# PCB1.net
KiCad netlist of a schematic drawn in EAGLE
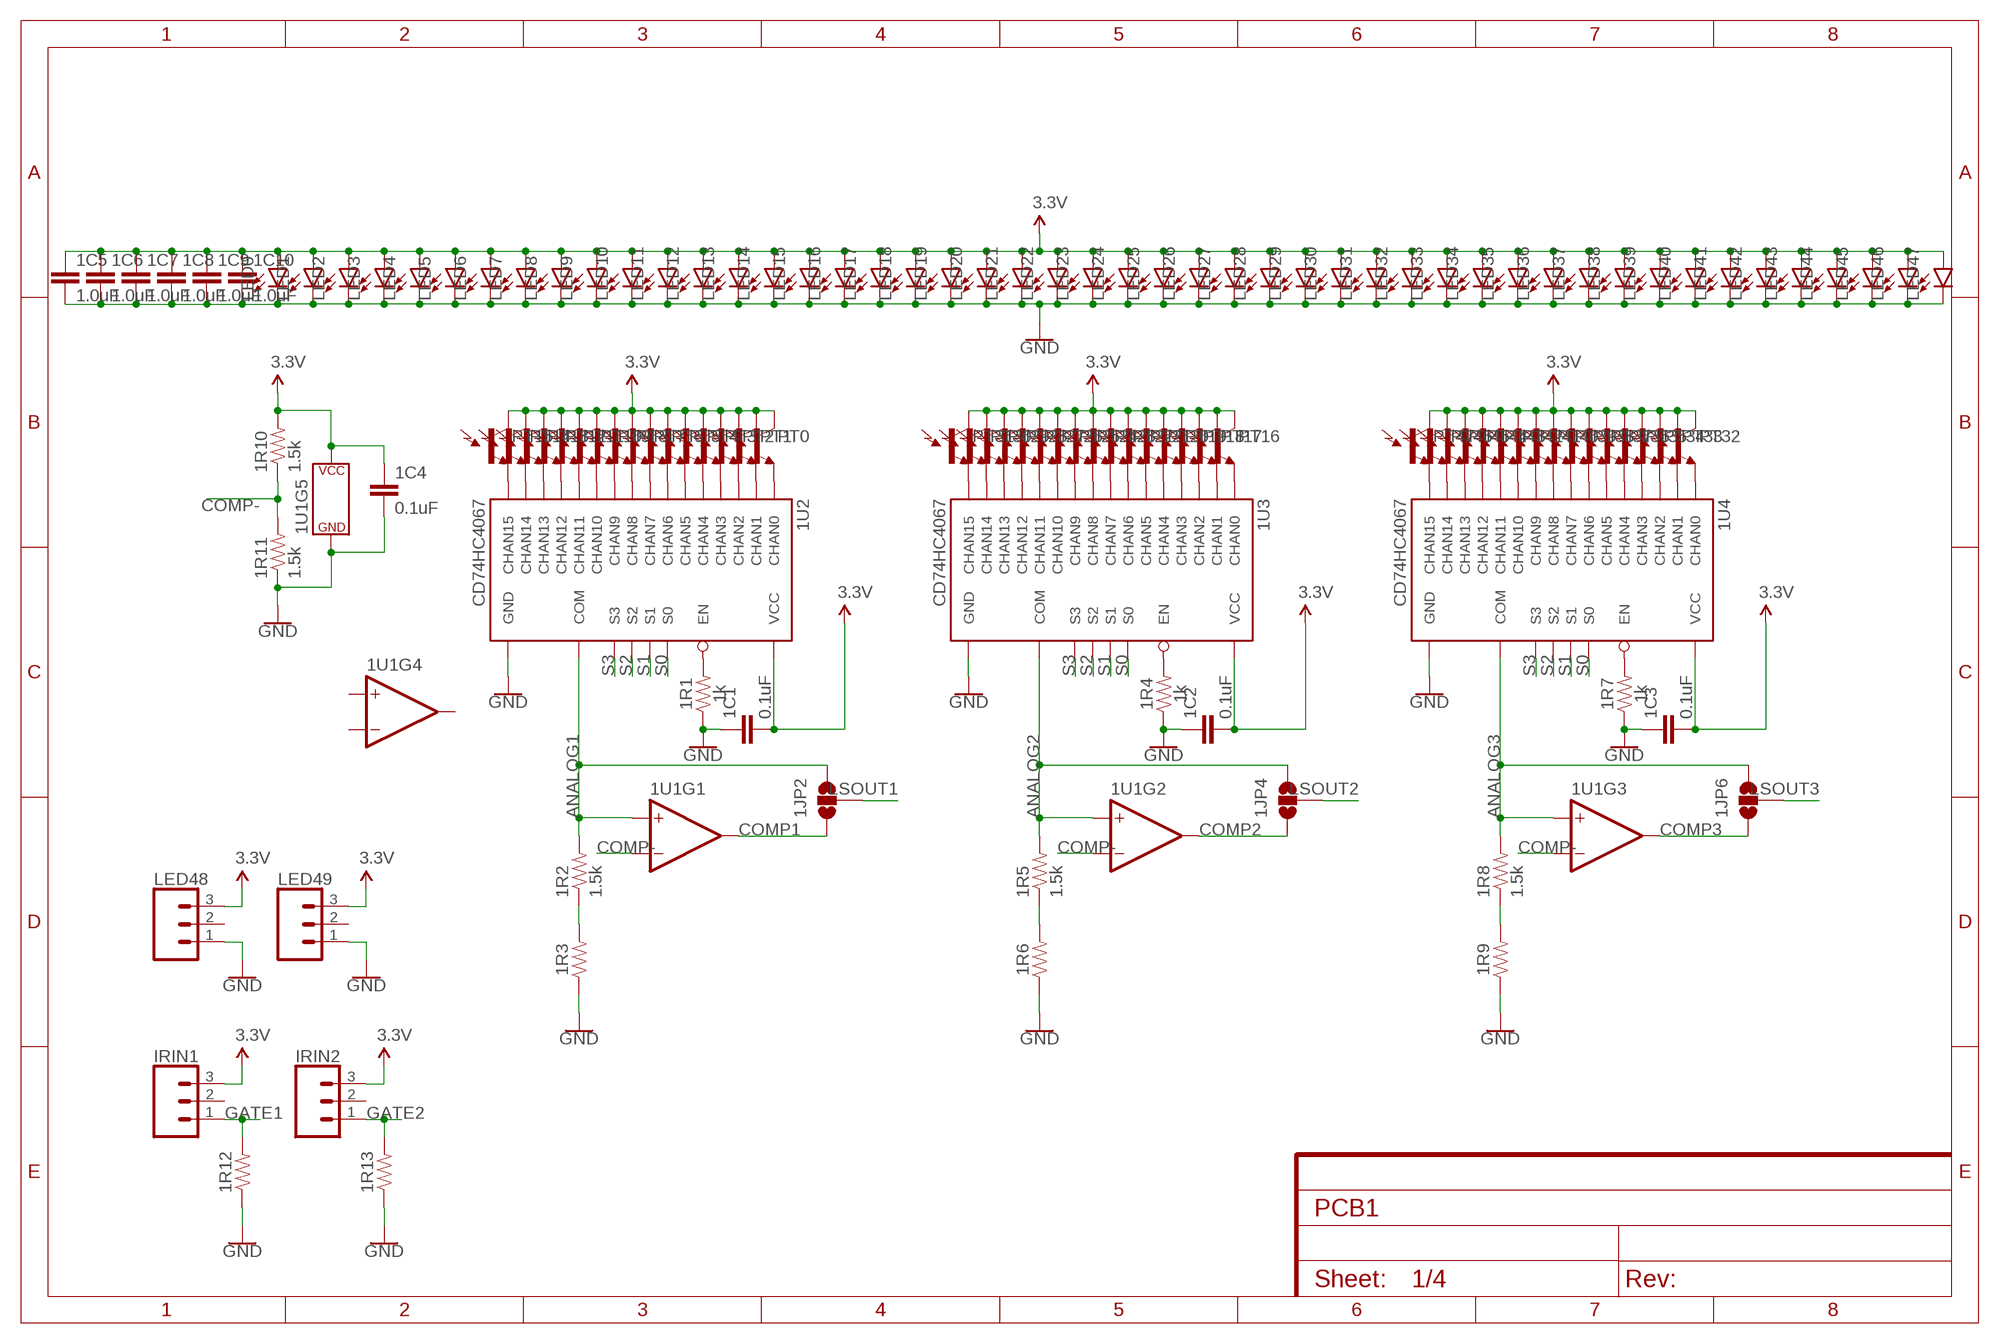
[diagram p0: schematic, sheet 1]
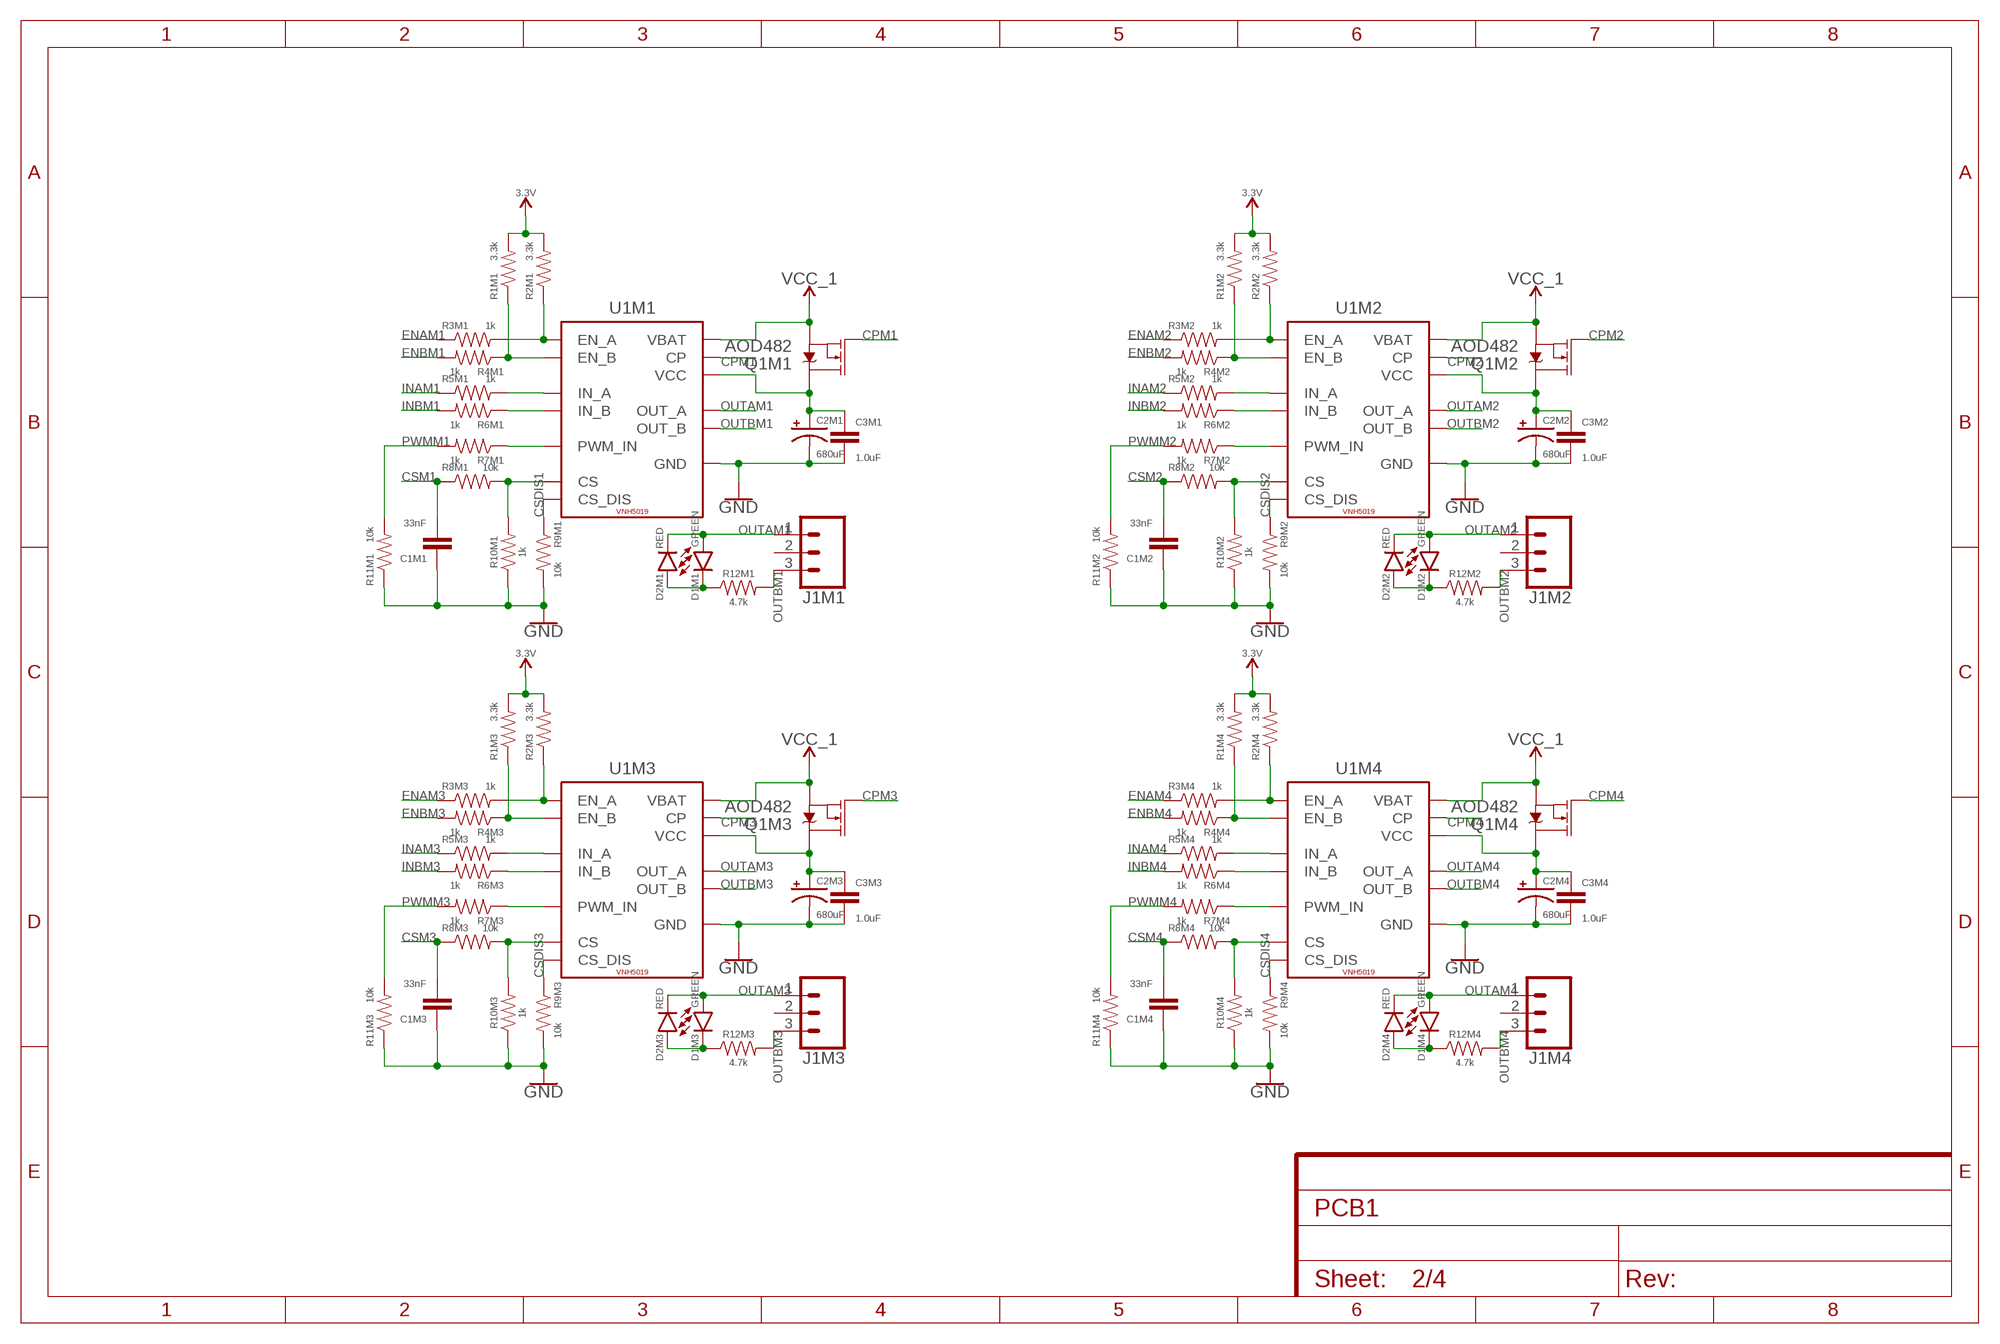
[diagram p1: schematic, sheet 2]
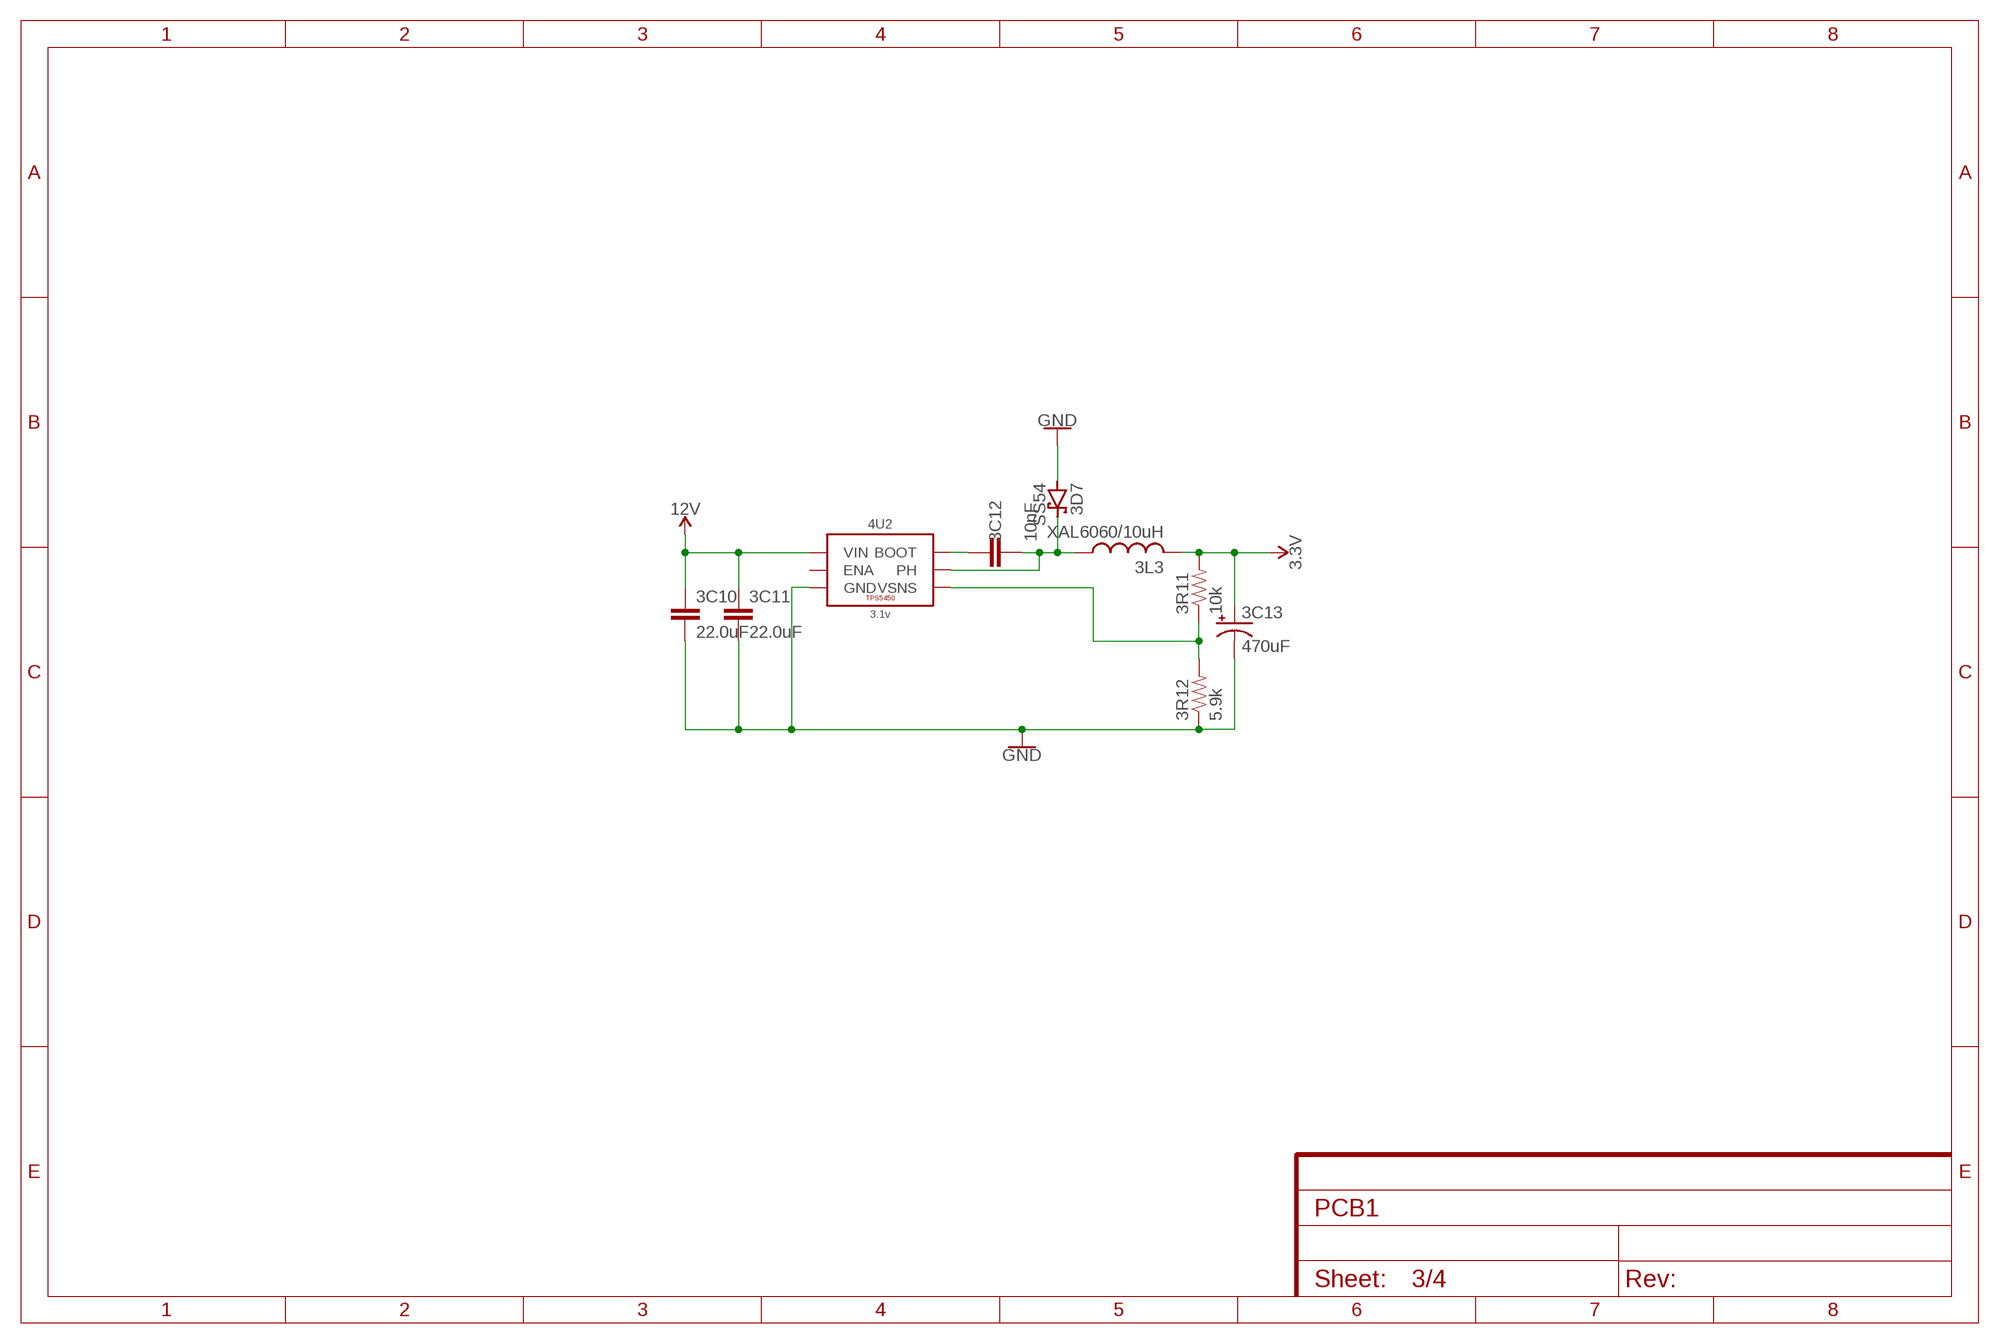
[diagram p2: schematic, sheet 3]
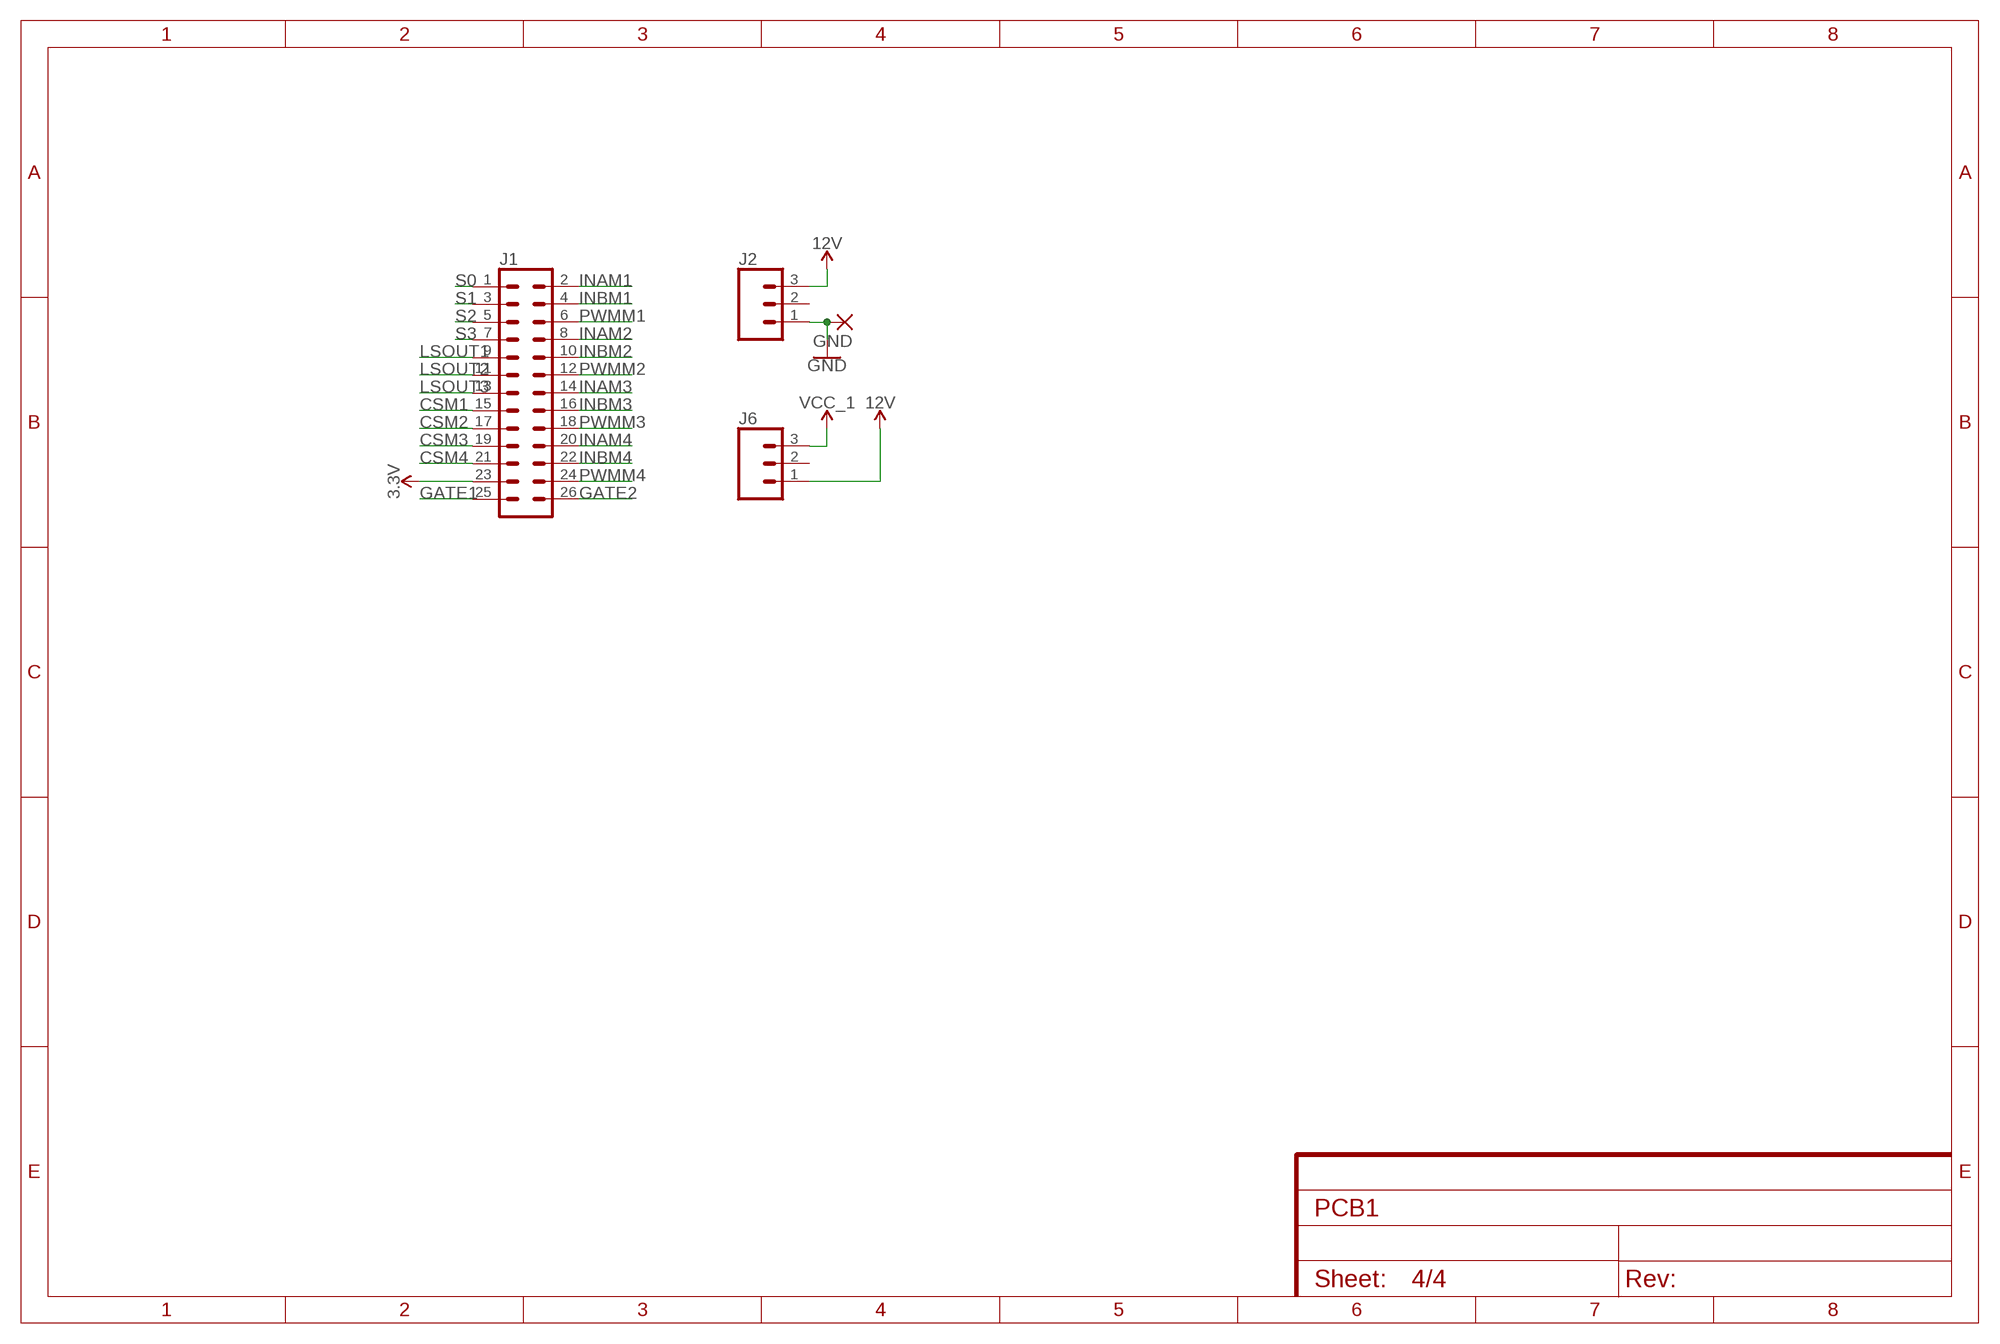
[diagram p3: schematic, sheet 4]

(export (version "E")
  (design (tool "Eeschema 10.0.6"))
  (components
    (comp (ref "C1M1")
      (value "33nF")
      (footprint "eagle-import:0603")
      (libsource (lib "eagle-import") (part "33NF-0603-50V-10%"))
    )
    (comp (ref "C1M2")
      (value "33nF")
      (footprint "eagle-import:0603")
      (libsource (lib "eagle-import") (part "33NF-0603-50V-10%"))
    )
    (comp (ref "C1M3")
      (value "33nF")
      (footprint "eagle-import:0603")
      (libsource (lib "eagle-import") (part "33NF-0603-50V-10%"))
    )
    (comp (ref "C1M4")
      (value "33nF")
      (footprint "eagle-import:0603")
      (libsource (lib "eagle-import") (part "33NF-0603-50V-10%"))
    )
    (comp (ref "C2M1")
      (value "680uF")
      (footprint "eagle-import:E3,5-8")
      (libsource (lib "eagle-import") (part "CPOL-USE3.5-8"))
    )
    (comp (ref "C2M2")
      (value "680uF")
      (footprint "eagle-import:E3,5-8")
      (libsource (lib "eagle-import") (part "CPOL-USE3.5-8"))
    )
    (comp (ref "C2M3")
      (value "680uF")
      (footprint "eagle-import:E3,5-8")
      (libsource (lib "eagle-import") (part "CPOL-USE3.5-8"))
    )
    (comp (ref "C2M4")
      (value "680uF")
      (footprint "eagle-import:E3,5-8")
      (libsource (lib "eagle-import") (part "CPOL-USE3.5-8"))
    )
    (comp (ref "C3M1")
      (value "1.0uF")
      (footprint "eagle-import:0603")
      (libsource (lib "eagle-import") (part "1.0UF-0603-16V-10%-X7R"))
    )
    (comp (ref "C3M2")
      (value "1.0uF")
      (footprint "eagle-import:0603")
      (libsource (lib "eagle-import") (part "1.0UF-0603-16V-10%-X7R"))
    )
    (comp (ref "C3M3")
      (value "1.0uF")
      (footprint "eagle-import:0603")
      (libsource (lib "eagle-import") (part "1.0UF-0603-16V-10%-X7R"))
    )
    (comp (ref "C3M4")
      (value "1.0uF")
      (footprint "eagle-import:0603")
      (libsource (lib "eagle-import") (part "1.0UF-0603-16V-10%-X7R"))
    )
    (comp (ref "D1M1")
      (value "GREEN")
      (footprint "eagle-import:LED-0603")
      (libsource (lib "eagle-import") (part "LED-GREEN0603"))
    )
    (comp (ref "D1M2")
      (value "GREEN")
      (footprint "eagle-import:LED-0603")
      (libsource (lib "eagle-import") (part "LED-GREEN0603"))
    )
    (comp (ref "D1M3")
      (value "GREEN")
      (footprint "eagle-import:LED-0603")
      (libsource (lib "eagle-import") (part "LED-GREEN0603"))
    )
    (comp (ref "D1M4")
      (value "GREEN")
      (footprint "eagle-import:LED-0603")
      (libsource (lib "eagle-import") (part "LED-GREEN0603"))
    )
    (comp (ref "D2M1")
      (value "RED")
      (footprint "eagle-import:LED-0603")
      (libsource (lib "eagle-import") (part "LED-RED0603"))
    )
    (comp (ref "D2M2")
      (value "RED")
      (footprint "eagle-import:LED-0603")
      (libsource (lib "eagle-import") (part "LED-RED0603"))
    )
    (comp (ref "D2M3")
      (value "RED")
      (footprint "eagle-import:LED-0603")
      (libsource (lib "eagle-import") (part "LED-RED0603"))
    )
    (comp (ref "D2M4")
      (value "RED")
      (footprint "eagle-import:LED-0603")
      (libsource (lib "eagle-import") (part "LED-RED0603"))
    )
    (comp (ref "J1M1")
      (value "CONN_03-SCREW-5MM")
      (footprint "eagle-import:SCREWTERMINAL-5MM-3")
      (libsource (lib "eagle-import") (part "CONN_03-SCREW-5MM"))
    )
    (comp (ref "J1M2")
      (value "CONN_03-SCREW-5MM")
      (footprint "eagle-import:SCREWTERMINAL-5MM-3")
      (libsource (lib "eagle-import") (part "CONN_03-SCREW-5MM"))
    )
    (comp (ref "J1M3")
      (value "CONN_03-SCREW-5MM")
      (footprint "eagle-import:SCREWTERMINAL-5MM-3")
      (libsource (lib "eagle-import") (part "CONN_03-SCREW-5MM"))
    )
    (comp (ref "J1M4")
      (value "CONN_03-SCREW-5MM")
      (footprint "eagle-import:SCREWTERMINAL-5MM-3")
      (libsource (lib "eagle-import") (part "CONN_03-SCREW-5MM"))
    )
    (comp (ref "Q1M1")
      (value "AOD482")
      (footprint "eagle-import:DPAK")
      (libsource (lib "eagle-import") (part "MOSFET-NCH-FDD8780"))
    )
    (comp (ref "Q1M2")
      (value "AOD482")
      (footprint "eagle-import:DPAK")
      (libsource (lib "eagle-import") (part "MOSFET-NCH-FDD8780"))
    )
    (comp (ref "Q1M3")
      (value "AOD482")
      (footprint "eagle-import:DPAK")
      (libsource (lib "eagle-import") (part "MOSFET-NCH-FDD8780"))
    )
    (comp (ref "Q1M4")
      (value "AOD482")
      (footprint "eagle-import:DPAK")
      (libsource (lib "eagle-import") (part "MOSFET-NCH-FDD8780"))
    )
    (comp (ref "R1M1")
      (value "3.3k")
      (footprint "eagle-import:0603")
      (libsource (lib "eagle-import") (part "3.3KOHM-0603-1/10W-1%"))
    )
    (comp (ref "R1M2")
      (value "3.3k")
      (footprint "eagle-import:0603")
      (libsource (lib "eagle-import") (part "3.3KOHM-0603-1/10W-1%"))
    )
    (comp (ref "R1M3")
      (value "3.3k")
      (footprint "eagle-import:0603")
      (libsource (lib "eagle-import") (part "3.3KOHM-0603-1/10W-1%"))
    )
    (comp (ref "R1M4")
      (value "3.3k")
      (footprint "eagle-import:0603")
      (libsource (lib "eagle-import") (part "3.3KOHM-0603-1/10W-1%"))
    )
    (comp (ref "R2M1")
      (value "3.3k")
      (footprint "eagle-import:0603")
      (libsource (lib "eagle-import") (part "3.3KOHM-0603-1/10W-1%"))
    )
    (comp (ref "R2M2")
      (value "3.3k")
      (footprint "eagle-import:0603")
      (libsource (lib "eagle-import") (part "3.3KOHM-0603-1/10W-1%"))
    )
    (comp (ref "R2M3")
      (value "3.3k")
      (footprint "eagle-import:0603")
      (libsource (lib "eagle-import") (part "3.3KOHM-0603-1/10W-1%"))
    )
    (comp (ref "R2M4")
      (value "3.3k")
      (footprint "eagle-import:0603")
      (libsource (lib "eagle-import") (part "3.3KOHM-0603-1/10W-1%"))
    )
    (comp (ref "R3M1")
      (value "1k")
      (footprint "eagle-import:0603")
      (libsource (lib "eagle-import") (part "1KOHM-0603-1/10W-1%"))
    )
    (comp (ref "R3M2")
      (value "1k")
      (footprint "eagle-import:0603")
      (libsource (lib "eagle-import") (part "1KOHM-0603-1/10W-1%"))
    )
    (comp (ref "R3M3")
      (value "1k")
      (footprint "eagle-import:0603")
      (libsource (lib "eagle-import") (part "1KOHM-0603-1/10W-1%"))
    )
    (comp (ref "R3M4")
      (value "1k")
      (footprint "eagle-import:0603")
      (libsource (lib "eagle-import") (part "1KOHM-0603-1/10W-1%"))
    )
    (comp (ref "R4M1")
      (value "1k")
      (footprint "eagle-import:0603")
      (libsource (lib "eagle-import") (part "1KOHM-0603-1/10W-1%"))
    )
    (comp (ref "R4M2")
      (value "1k")
      (footprint "eagle-import:0603")
      (libsource (lib "eagle-import") (part "1KOHM-0603-1/10W-1%"))
    )
    (comp (ref "R4M3")
      (value "1k")
      (footprint "eagle-import:0603")
      (libsource (lib "eagle-import") (part "1KOHM-0603-1/10W-1%"))
    )
    (comp (ref "R4M4")
      (value "1k")
      (footprint "eagle-import:0603")
      (libsource (lib "eagle-import") (part "1KOHM-0603-1/10W-1%"))
    )
    (comp (ref "R5M1")
      (value "1k")
      (footprint "eagle-import:0603")
      (libsource (lib "eagle-import") (part "1KOHM-0603-1/10W-1%"))
    )
    (comp (ref "R5M2")
      (value "1k")
      (footprint "eagle-import:0603")
      (libsource (lib "eagle-import") (part "1KOHM-0603-1/10W-1%"))
    )
    (comp (ref "R5M3")
      (value "1k")
      (footprint "eagle-import:0603")
      (libsource (lib "eagle-import") (part "1KOHM-0603-1/10W-1%"))
    )
    (comp (ref "R5M4")
      (value "1k")
      (footprint "eagle-import:0603")
      (libsource (lib "eagle-import") (part "1KOHM-0603-1/10W-1%"))
    )
    (comp (ref "R6M1")
      (value "1k")
      (footprint "eagle-import:0603")
      (libsource (lib "eagle-import") (part "1KOHM-0603-1/10W-1%"))
    )
    (comp (ref "R6M2")
      (value "1k")
      (footprint "eagle-import:0603")
      (libsource (lib "eagle-import") (part "1KOHM-0603-1/10W-1%"))
    )
    (comp (ref "R6M3")
      (value "1k")
      (footprint "eagle-import:0603")
      (libsource (lib "eagle-import") (part "1KOHM-0603-1/10W-1%"))
    )
    (comp (ref "R6M4")
      (value "1k")
      (footprint "eagle-import:0603")
      (libsource (lib "eagle-import") (part "1KOHM-0603-1/10W-1%"))
    )
    (comp (ref "R7M1")
      (value "1k")
      (footprint "eagle-import:0603")
      (libsource (lib "eagle-import") (part "1KOHM-0603-1/10W-1%"))
    )
    (comp (ref "R7M2")
      (value "1k")
      (footprint "eagle-import:0603")
      (libsource (lib "eagle-import") (part "1KOHM-0603-1/10W-1%"))
    )
    (comp (ref "R7M3")
      (value "1k")
      (footprint "eagle-import:0603")
      (libsource (lib "eagle-import") (part "1KOHM-0603-1/10W-1%"))
    )
    (comp (ref "R7M4")
      (value "1k")
      (footprint "eagle-import:0603")
      (libsource (lib "eagle-import") (part "1KOHM-0603-1/10W-1%"))
    )
    (comp (ref "R8M1")
      (value "10k")
      (footprint "eagle-import:0603")
      (libsource (lib "eagle-import") (part "10KOHM-0603-1/10W-1%"))
    )
    (comp (ref "R8M2")
      (value "10k")
      (footprint "eagle-import:0603")
      (libsource (lib "eagle-import") (part "10KOHM-0603-1/10W-1%"))
    )
    (comp (ref "R8M3")
      (value "10k")
      (footprint "eagle-import:0603")
      (libsource (lib "eagle-import") (part "10KOHM-0603-1/10W-1%"))
    )
    (comp (ref "R8M4")
      (value "10k")
      (footprint "eagle-import:0603")
      (libsource (lib "eagle-import") (part "10KOHM-0603-1/10W-1%"))
    )
    (comp (ref "R9M1")
      (value "10k")
      (footprint "eagle-import:0603")
      (libsource (lib "eagle-import") (part "10KOHM-0603-1/10W-1%"))
    )
    (comp (ref "R9M2")
      (value "10k")
      (footprint "eagle-import:0603")
      (libsource (lib "eagle-import") (part "10KOHM-0603-1/10W-1%"))
    )
    (comp (ref "R9M3")
      (value "10k")
      (footprint "eagle-import:0603")
      (libsource (lib "eagle-import") (part "10KOHM-0603-1/10W-1%"))
    )
    (comp (ref "R9M4")
      (value "10k")
      (footprint "eagle-import:0603")
      (libsource (lib "eagle-import") (part "10KOHM-0603-1/10W-1%"))
    )
    (comp (ref "R10M1")
      (value "1k")
      (footprint "eagle-import:0603")
      (libsource (lib "eagle-import") (part "1KOHM-0603-1/10W-1%"))
    )
    (comp (ref "R10M2")
      (value "1k")
      (footprint "eagle-import:0603")
      (libsource (lib "eagle-import") (part "1KOHM-0603-1/10W-1%"))
    )
    (comp (ref "R10M3")
      (value "1k")
      (footprint "eagle-import:0603")
      (libsource (lib "eagle-import") (part "1KOHM-0603-1/10W-1%"))
    )
    (comp (ref "R10M4")
      (value "1k")
      (footprint "eagle-import:0603")
      (libsource (lib "eagle-import") (part "1KOHM-0603-1/10W-1%"))
    )
    (comp (ref "R11M1")
      (value "10k")
      (footprint "eagle-import:0603")
      (libsource (lib "eagle-import") (part "10KOHM-0603-1/10W-1%"))
    )
    (comp (ref "R11M2")
      (value "10k")
      (footprint "eagle-import:0603")
      (libsource (lib "eagle-import") (part "10KOHM-0603-1/10W-1%"))
    )
    (comp (ref "R11M3")
      (value "10k")
      (footprint "eagle-import:0603")
      (libsource (lib "eagle-import") (part "10KOHM-0603-1/10W-1%"))
    )
    (comp (ref "R11M4")
      (value "10k")
      (footprint "eagle-import:0603")
      (libsource (lib "eagle-import") (part "10KOHM-0603-1/10W-1%"))
    )
    (comp (ref "R12M1")
      (value "4.7k")
      (footprint "eagle-import:0603")
      (libsource (lib "eagle-import") (part "4.7KOHM-0603-1/10W-1%"))
    )
    (comp (ref "R12M2")
      (value "4.7k")
      (footprint "eagle-import:0603")
      (libsource (lib "eagle-import") (part "4.7KOHM-0603-1/10W-1%"))
    )
    (comp (ref "R12M3")
      (value "4.7k")
      (footprint "eagle-import:0603")
      (libsource (lib "eagle-import") (part "4.7KOHM-0603-1/10W-1%"))
    )
    (comp (ref "R12M4")
      (value "4.7k")
      (footprint "eagle-import:0603")
      (libsource (lib "eagle-import") (part "4.7KOHM-0603-1/10W-1%"))
    )
    (comp (ref "U1M1")
      (value "VNH5019")
      (footprint "eagle-import:POWERSO-30")
      (libsource (lib "eagle-import") (part "VNH5019"))
    )
    (comp (ref "U1M2")
      (value "VNH5019")
      (footprint "eagle-import:POWERSO-30")
      (libsource (lib "eagle-import") (part "VNH5019"))
    )
    (comp (ref "U1M3")
      (value "VNH5019")
      (footprint "eagle-import:POWERSO-30")
      (libsource (lib "eagle-import") (part "VNH5019"))
    )
    (comp (ref "U1M4")
      (value "VNH5019")
      (footprint "eagle-import:POWERSO-30")
      (libsource (lib "eagle-import") (part "VNH5019"))
    )
    (comp (ref "1C1")
      (value "0.1uF")
      (footprint "eagle-import:0603")
      (libsource (lib "eagle-import") (part "0.1UF-0603-25V-5%"))
    )
    (comp (ref "1C2")
      (value "0.1uF")
      (footprint "eagle-import:0603")
      (libsource (lib "eagle-import") (part "0.1UF-0603-25V-5%"))
    )
    (comp (ref "1C3")
      (value "0.1uF")
      (footprint "eagle-import:0603")
      (libsource (lib "eagle-import") (part "0.1UF-0603-25V-5%"))
    )
    (comp (ref "1C4")
      (value "0.1uF")
      (footprint "eagle-import:0603")
      (libsource (lib "eagle-import") (part "0.1UF-0603-25V-5%"))
    )
    (comp (ref "1C5")
      (value "1.0uF")
      (footprint "eagle-import:0603")
      (libsource (lib "eagle-import") (part "1.0UF-0603-16V-10%-X7R"))
    )
    (comp (ref "1C6")
      (value "1.0uF")
      (footprint "eagle-import:0603")
      (libsource (lib "eagle-import") (part "1.0UF-0603-16V-10%-X7R"))
    )
    (comp (ref "1C7")
      (value "1.0uF")
      (footprint "eagle-import:0603")
      (libsource (lib "eagle-import") (part "1.0UF-0603-16V-10%-X7R"))
    )
    (comp (ref "1C8")
      (value "1.0uF")
      (footprint "eagle-import:0603")
      (libsource (lib "eagle-import") (part "1.0UF-0603-16V-10%-X7R"))
    )
    (comp (ref "1C9")
      (value "1.0uF")
      (footprint "eagle-import:0603")
      (libsource (lib "eagle-import") (part "1.0UF-0603-16V-10%-X7R"))
    )
    (comp (ref "1C10")
      (value "1.0uF")
      (footprint "eagle-import:0603")
      (libsource (lib "eagle-import") (part "1.0UF-0603-16V-10%-X7R"))
    )
    (comp (ref "1JP2")
      (value "JUMPER-SMT_3_NO_NO_SILK")
      (footprint "eagle-import:SMT-JUMPER_3_0-NO_TRACE_NO-SILK")
      (libsource (lib "eagle-import") (part "JUMPER-SMT_3_NO_NO_SILK"))
    )
    (comp (ref "1JP4")
      (value "JUMPER-SMT_3_NO_NO_SILK")
      (footprint "eagle-import:SMT-JUMPER_3_0-NO_TRACE_NO-SILK")
      (libsource (lib "eagle-import") (part "JUMPER-SMT_3_NO_NO_SILK"))
    )
    (comp (ref "1JP6")
      (value "JUMPER-SMT_3_NO_NO_SILK")
      (footprint "eagle-import:SMT-JUMPER_3_0-NO_TRACE_NO-SILK")
      (libsource (lib "eagle-import") (part "JUMPER-SMT_3_NO_NO_SILK"))
    )
    (comp (ref "1R1")
      (value "1k")
      (footprint "eagle-import:0603")
      (libsource (lib "eagle-import") (part "1KOHM-0603-1/10W-1%"))
    )
    (comp (ref "1R2")
      (value "1.5k")
      (footprint "eagle-import:0603")
      (libsource (lib "eagle-import") (part "1.5KOHM-0603-1/10W-1%"))
    )
    (comp (ref "1R3")
      (value "RESISTOR0603")
      (footprint "eagle-import:0603")
      (libsource (lib "eagle-import") (part "RESISTOR0603"))
    )
    (comp (ref "1R4")
      (value "1k")
      (footprint "eagle-import:0603")
      (libsource (lib "eagle-import") (part "1KOHM-0603-1/10W-1%"))
    )
    (comp (ref "1R5")
      (value "1.5k")
      (footprint "eagle-import:0603")
      (libsource (lib "eagle-import") (part "1.5KOHM-0603-1/10W-1%"))
    )
    (comp (ref "1R6")
      (value "RESISTOR0603")
      (footprint "eagle-import:0603")
      (libsource (lib "eagle-import") (part "RESISTOR0603"))
    )
    (comp (ref "1R7")
      (value "1k")
      (footprint "eagle-import:0603")
      (libsource (lib "eagle-import") (part "1KOHM-0603-1/10W-1%"))
    )
    (comp (ref "1R8")
      (value "1.5k")
      (footprint "eagle-import:0603")
      (libsource (lib "eagle-import") (part "1.5KOHM-0603-1/10W-1%"))
    )
    (comp (ref "1R9")
      (value "RESISTOR0603")
      (footprint "eagle-import:0603")
      (libsource (lib "eagle-import") (part "RESISTOR0603"))
    )
    (comp (ref "1R10")
      (value "1.5k")
      (footprint "eagle-import:0603")
      (libsource (lib "eagle-import") (part "1.5KOHM-0603-1/10W-1%"))
    )
    (comp (ref "1R11")
      (value "1.5k")
      (footprint "eagle-import:0603")
      (libsource (lib "eagle-import") (part "1.5KOHM-0603-1/10W-1%"))
    )
    (comp (ref "1R12")
      (value "RESISTOR0603")
      (footprint "eagle-import:0603")
      (libsource (lib "eagle-import") (part "RESISTOR0603"))
    )
    (comp (ref "1R13")
      (value "RESISTOR0603")
      (footprint "eagle-import:0603")
      (libsource (lib "eagle-import") (part "RESISTOR0603"))
    )
    (comp (ref "1U1")
      (value "LM339")
      (footprint "eagle-import:SOIC-14")
      (libsource (lib "eagle-import") (part "LM339"))
    )
    (comp (ref "1U2")
      (value "CD74HC4067")
      (footprint "eagle-import:SOIC-24")
      (libsource (lib "eagle-import") (part "CD74HC4067"))
    )
    (comp (ref "1U3")
      (value "CD74HC4067")
      (footprint "eagle-import:SOIC-24")
      (libsource (lib "eagle-import") (part "CD74HC4067"))
    )
    (comp (ref "1U4")
      (value "CD74HC4067")
      (footprint "eagle-import:SOIC-24")
      (libsource (lib "eagle-import") (part "CD74HC4067"))
    )
    (comp (ref "IRIN1")
      (value "CONN_03")
      (footprint "eagle-import:1X03")
      (libsource (lib "eagle-import") (part "SparkFun-Connectors_513_CONN_03"))
    )
    (comp (ref "IRIN2")
      (value "CONN_03")
      (footprint "eagle-import:1X03")
      (libsource (lib "eagle-import") (part "SparkFun-Connectors_513_CONN_03"))
    )
    (comp (ref "LED0")
      (value "3528LED")
      (footprint "eagle-import:3528")
      (libsource (lib "eagle-import") (part "3528LED"))
    )
    (comp (ref "LED1")
      (value "3528LED")
      (footprint "eagle-import:3528")
      (libsource (lib "eagle-import") (part "3528LED"))
    )
    (comp (ref "LED2")
      (value "3528LED")
      (footprint "eagle-import:3528")
      (libsource (lib "eagle-import") (part "3528LED"))
    )
    (comp (ref "LED3")
      (value "3528LED")
      (footprint "eagle-import:3528")
      (libsource (lib "eagle-import") (part "3528LED"))
    )
    (comp (ref "LED4")
      (value "3528LED")
      (footprint "eagle-import:3528")
      (libsource (lib "eagle-import") (part "3528LED"))
    )
    (comp (ref "LED5")
      (value "3528LED")
      (footprint "eagle-import:3528")
      (libsource (lib "eagle-import") (part "3528LED"))
    )
    (comp (ref "LED6")
      (value "3528LED")
      (footprint "eagle-import:3528")
      (libsource (lib "eagle-import") (part "3528LED"))
    )
    (comp (ref "LED7")
      (value "3528LED")
      (footprint "eagle-import:3528")
      (libsource (lib "eagle-import") (part "3528LED"))
    )
    (comp (ref "LED8")
      (value "3528LED")
      (footprint "eagle-import:3528")
      (libsource (lib "eagle-import") (part "3528LED"))
    )
    (comp (ref "LED9")
      (value "3528LED")
      (footprint "eagle-import:3528")
      (libsource (lib "eagle-import") (part "3528LED"))
    )
    (comp (ref "LED10")
      (value "3528LED")
      (footprint "eagle-import:3528")
      (libsource (lib "eagle-import") (part "3528LED"))
    )
    (comp (ref "LED11")
      (value "3528LED")
      (footprint "eagle-import:3528")
      (libsource (lib "eagle-import") (part "3528LED"))
    )
    (comp (ref "LED12")
      (value "3528LED")
      (footprint "eagle-import:3528")
      (libsource (lib "eagle-import") (part "3528LED"))
    )
    (comp (ref "LED13")
      (value "3528LED")
      (footprint "eagle-import:3528")
      (libsource (lib "eagle-import") (part "3528LED"))
    )
    (comp (ref "LED14")
      (value "3528LED")
      (footprint "eagle-import:3528")
      (libsource (lib "eagle-import") (part "3528LED"))
    )
    (comp (ref "LED15")
      (value "3528LED")
      (footprint "eagle-import:3528")
      (libsource (lib "eagle-import") (part "3528LED"))
    )
    (comp (ref "LED16")
      (value "3528LED")
      (footprint "eagle-import:3528")
      (libsource (lib "eagle-import") (part "3528LED"))
    )
    (comp (ref "LED17")
      (value "3528LED")
      (footprint "eagle-import:3528")
      (libsource (lib "eagle-import") (part "3528LED"))
    )
    (comp (ref "LED18")
      (value "3528LED")
      (footprint "eagle-import:3528")
      (libsource (lib "eagle-import") (part "3528LED"))
    )
    (comp (ref "LED19")
      (value "3528LED")
      (footprint "eagle-import:3528")
      (libsource (lib "eagle-import") (part "3528LED"))
    )
    (comp (ref "LED20")
      (value "3528LED")
      (footprint "eagle-import:3528")
      (libsource (lib "eagle-import") (part "3528LED"))
    )
    (comp (ref "LED21")
      (value "3528LED")
      (footprint "eagle-import:3528")
      (libsource (lib "eagle-import") (part "3528LED"))
    )
    (comp (ref "LED22")
      (value "3528LED")
      (footprint "eagle-import:3528")
      (libsource (lib "eagle-import") (part "3528LED"))
    )
    (comp (ref "LED23")
      (value "3528LED")
      (footprint "eagle-import:3528")
      (libsource (lib "eagle-import") (part "3528LED"))
    )
    (comp (ref "LED24")
      (value "3528LED")
      (footprint "eagle-import:3528")
      (libsource (lib "eagle-import") (part "3528LED"))
    )
    (comp (ref "LED25")
      (value "3528LED")
      (footprint "eagle-import:3528")
      (libsource (lib "eagle-import") (part "3528LED"))
    )
    (comp (ref "LED26")
      (value "3528LED")
      (footprint "eagle-import:3528")
      (libsource (lib "eagle-import") (part "3528LED"))
    )
    (comp (ref "LED27")
      (value "3528LED")
      (footprint "eagle-import:3528")
      (libsource (lib "eagle-import") (part "3528LED"))
    )
    (comp (ref "LED28")
      (value "3528LED")
      (footprint "eagle-import:3528")
      (libsource (lib "eagle-import") (part "3528LED"))
    )
    (comp (ref "LED29")
      (value "3528LED")
      (footprint "eagle-import:3528")
      (libsource (lib "eagle-import") (part "3528LED"))
    )
    (comp (ref "LED30")
      (value "3528LED")
      (footprint "eagle-import:3528")
      (libsource (lib "eagle-import") (part "3528LED"))
    )
    (comp (ref "LED31")
      (value "3528LED")
      (footprint "eagle-import:3528")
      (libsource (lib "eagle-import") (part "3528LED"))
    )
    (comp (ref "LED32")
      (value "3528LED")
      (footprint "eagle-import:3528")
      (libsource (lib "eagle-import") (part "3528LED"))
    )
    (comp (ref "LED33")
      (value "3528LED")
      (footprint "eagle-import:3528")
      (libsource (lib "eagle-import") (part "3528LED"))
    )
    (comp (ref "LED34")
      (value "3528LED")
      (footprint "eagle-import:3528")
      (libsource (lib "eagle-import") (part "3528LED"))
    )
    (comp (ref "LED35")
      (value "3528LED")
      (footprint "eagle-import:3528")
      (libsource (lib "eagle-import") (part "3528LED"))
    )
    (comp (ref "LED36")
      (value "3528LED")
      (footprint "eagle-import:3528")
      (libsource (lib "eagle-import") (part "3528LED"))
    )
    (comp (ref "LED37")
      (value "3528LED")
      (footprint "eagle-import:3528")
      (libsource (lib "eagle-import") (part "3528LED"))
    )
    (comp (ref "LED38")
      (value "3528LED")
      (footprint "eagle-import:3528")
      (libsource (lib "eagle-import") (part "3528LED"))
    )
    (comp (ref "LED39")
      (value "3528LED")
      (footprint "eagle-import:3528")
      (libsource (lib "eagle-import") (part "3528LED"))
    )
    (comp (ref "LED40")
      (value "3528LED")
      (footprint "eagle-import:3528")
      (libsource (lib "eagle-import") (part "3528LED"))
    )
    (comp (ref "LED41")
      (value "3528LED")
      (footprint "eagle-import:3528")
      (libsource (lib "eagle-import") (part "3528LED"))
    )
    (comp (ref "LED42")
      (value "3528LED")
      (footprint "eagle-import:3528")
      (libsource (lib "eagle-import") (part "3528LED"))
    )
    (comp (ref "LED43")
      (value "3528LED")
      (footprint "eagle-import:3528")
      (libsource (lib "eagle-import") (part "3528LED"))
    )
    (comp (ref "LED44")
      (value "3528LED")
      (footprint "eagle-import:3528")
      (libsource (lib "eagle-import") (part "3528LED"))
    )
    (comp (ref "LED45")
      (value "3528LED")
      (footprint "eagle-import:3528")
      (libsource (lib "eagle-import") (part "3528LED"))
    )
    (comp (ref "LED46")
      (value "3528LED")
      (footprint "eagle-import:3528")
      (libsource (lib "eagle-import") (part "3528LED"))
    )
    (comp (ref "LED47")
      (value "3528LED")
      (footprint "eagle-import:3528")
      (libsource (lib "eagle-import") (part "3528LED"))
    )
    (comp (ref "LED48")
      (value "CONN_03")
      (footprint "eagle-import:1X03")
      (libsource (lib "eagle-import") (part "SparkFun-Connectors_513_CONN_03"))
    )
    (comp (ref "LED49")
      (value "CONN_03")
      (footprint "eagle-import:1X03")
      (libsource (lib "eagle-import") (part "SparkFun-Connectors_513_CONN_03"))
    )
    (comp (ref "PT0")
      (value "TEMT6000")
      (footprint "eagle-import:TEMT6000")
      (libsource (lib "eagle-import") (part "LIGHT_SENSORTEMT6000"))
    )
    (comp (ref "PT1")
      (value "TEMT6000")
      (footprint "eagle-import:TEMT6000")
      (libsource (lib "eagle-import") (part "LIGHT_SENSORTEMT6000"))
    )
    (comp (ref "PT2")
      (value "TEMT6000")
      (footprint "eagle-import:TEMT6000")
      (libsource (lib "eagle-import") (part "LIGHT_SENSORTEMT6000"))
    )
    (comp (ref "PT3")
      (value "TEMT6000")
      (footprint "eagle-import:TEMT6000")
      (libsource (lib "eagle-import") (part "LIGHT_SENSORTEMT6000"))
    )
    (comp (ref "PT4")
      (value "TEMT6000")
      (footprint "eagle-import:TEMT6000")
      (libsource (lib "eagle-import") (part "LIGHT_SENSORTEMT6000"))
    )
    (comp (ref "PT5")
      (value "TEMT6000")
      (footprint "eagle-import:TEMT6000")
      (libsource (lib "eagle-import") (part "LIGHT_SENSORTEMT6000"))
    )
    (comp (ref "PT6")
      (value "TEMT6000")
      (footprint "eagle-import:TEMT6000")
      (libsource (lib "eagle-import") (part "LIGHT_SENSORTEMT6000"))
    )
    (comp (ref "PT7")
      (value "TEMT6000")
      (footprint "eagle-import:TEMT6000")
      (libsource (lib "eagle-import") (part "LIGHT_SENSORTEMT6000"))
    )
    (comp (ref "PT8")
      (value "TEMT6000")
      (footprint "eagle-import:TEMT6000")
      (libsource (lib "eagle-import") (part "LIGHT_SENSORTEMT6000"))
    )
    (comp (ref "PT9")
      (value "TEMT6000")
      (footprint "eagle-import:TEMT6000")
      (libsource (lib "eagle-import") (part "LIGHT_SENSORTEMT6000"))
    )
    (comp (ref "PT10")
      (value "TEMT6000")
      (footprint "eagle-import:TEMT6000")
      (libsource (lib "eagle-import") (part "LIGHT_SENSORTEMT6000"))
    )
    (comp (ref "PT11")
      (value "TEMT6000")
      (footprint "eagle-import:TEMT6000")
      (libsource (lib "eagle-import") (part "LIGHT_SENSORTEMT6000"))
    )
    (comp (ref "PT12")
      (value "TEMT6000")
      (footprint "eagle-import:TEMT6000")
      (libsource (lib "eagle-import") (part "LIGHT_SENSORTEMT6000"))
    )
    (comp (ref "PT13")
      (value "TEMT6000")
      (footprint "eagle-import:TEMT6000")
      (libsource (lib "eagle-import") (part "LIGHT_SENSORTEMT6000"))
    )
    (comp (ref "PT14")
      (value "TEMT6000")
      (footprint "eagle-import:TEMT6000")
      (libsource (lib "eagle-import") (part "LIGHT_SENSORTEMT6000"))
    )
    (comp (ref "PT15")
      (value "TEMT6000")
      (footprint "eagle-import:TEMT6000")
      (libsource (lib "eagle-import") (part "LIGHT_SENSORTEMT6000"))
    )
    (comp (ref "PT16")
      (value "TEMT6000")
      (footprint "eagle-import:TEMT6000")
      (libsource (lib "eagle-import") (part "LIGHT_SENSORTEMT6000"))
    )
    (comp (ref "PT17")
      (value "TEMT6000")
      (footprint "eagle-import:TEMT6000")
      (libsource (lib "eagle-import") (part "LIGHT_SENSORTEMT6000"))
    )
    (comp (ref "PT18")
      (value "TEMT6000")
      (footprint "eagle-import:TEMT6000")
      (libsource (lib "eagle-import") (part "LIGHT_SENSORTEMT6000"))
    )
    (comp (ref "PT19")
      (value "TEMT6000")
      (footprint "eagle-import:TEMT6000")
      (libsource (lib "eagle-import") (part "LIGHT_SENSORTEMT6000"))
    )
    (comp (ref "PT20")
      (value "TEMT6000")
      (footprint "eagle-import:TEMT6000")
      (libsource (lib "eagle-import") (part "LIGHT_SENSORTEMT6000"))
    )
    (comp (ref "PT21")
      (value "TEMT6000")
      (footprint "eagle-import:TEMT6000")
      (libsource (lib "eagle-import") (part "LIGHT_SENSORTEMT6000"))
    )
    (comp (ref "PT22")
      (value "TEMT6000")
      (footprint "eagle-import:TEMT6000")
      (libsource (lib "eagle-import") (part "LIGHT_SENSORTEMT6000"))
    )
    (comp (ref "PT23")
      (value "TEMT6000")
      (footprint "eagle-import:TEMT6000")
      (libsource (lib "eagle-import") (part "LIGHT_SENSORTEMT6000"))
    )
    (comp (ref "PT24")
      (value "TEMT6000")
      (footprint "eagle-import:TEMT6000")
      (libsource (lib "eagle-import") (part "LIGHT_SENSORTEMT6000"))
    )
    (comp (ref "PT25")
      (value "TEMT6000")
      (footprint "eagle-import:TEMT6000")
      (libsource (lib "eagle-import") (part "LIGHT_SENSORTEMT6000"))
    )
    (comp (ref "PT26")
      (value "TEMT6000")
      (footprint "eagle-import:TEMT6000")
      (libsource (lib "eagle-import") (part "LIGHT_SENSORTEMT6000"))
    )
    (comp (ref "PT27")
      (value "TEMT6000")
      (footprint "eagle-import:TEMT6000")
      (libsource (lib "eagle-import") (part "LIGHT_SENSORTEMT6000"))
    )
    (comp (ref "PT28")
      (value "TEMT6000")
      (footprint "eagle-import:TEMT6000")
      (libsource (lib "eagle-import") (part "LIGHT_SENSORTEMT6000"))
    )
    (comp (ref "PT29")
      (value "TEMT6000")
      (footprint "eagle-import:TEMT6000")
      (libsource (lib "eagle-import") (part "LIGHT_SENSORTEMT6000"))
    )
    (comp (ref "PT30")
      (value "TEMT6000")
      (footprint "eagle-import:TEMT6000")
      (libsource (lib "eagle-import") (part "LIGHT_SENSORTEMT6000"))
    )
    (comp (ref "PT31")
      (value "TEMT6000")
      (footprint "eagle-import:TEMT6000")
      (libsource (lib "eagle-import") (part "LIGHT_SENSORTEMT6000"))
    )
    (comp (ref "PT32")
      (value "TEMT6000")
      (footprint "eagle-import:TEMT6000")
      (libsource (lib "eagle-import") (part "LIGHT_SENSORTEMT6000"))
    )
    (comp (ref "PT33")
      (value "TEMT6000")
      (footprint "eagle-import:TEMT6000")
      (libsource (lib "eagle-import") (part "LIGHT_SENSORTEMT6000"))
    )
    (comp (ref "PT34")
      (value "TEMT6000")
      (footprint "eagle-import:TEMT6000")
      (libsource (lib "eagle-import") (part "LIGHT_SENSORTEMT6000"))
    )
    (comp (ref "PT35")
      (value "TEMT6000")
      (footprint "eagle-import:TEMT6000")
      (libsource (lib "eagle-import") (part "LIGHT_SENSORTEMT6000"))
    )
    (comp (ref "PT36")
      (value "TEMT6000")
      (footprint "eagle-import:TEMT6000")
      (libsource (lib "eagle-import") (part "LIGHT_SENSORTEMT6000"))
    )
    (comp (ref "PT37")
      (value "TEMT6000")
      (footprint "eagle-import:TEMT6000")
      (libsource (lib "eagle-import") (part "LIGHT_SENSORTEMT6000"))
    )
    (comp (ref "PT38")
      (value "TEMT6000")
      (footprint "eagle-import:TEMT6000")
      (libsource (lib "eagle-import") (part "LIGHT_SENSORTEMT6000"))
    )
    (comp (ref "PT39")
      (value "TEMT6000")
      (footprint "eagle-import:TEMT6000")
      (libsource (lib "eagle-import") (part "LIGHT_SENSORTEMT6000"))
    )
    (comp (ref "PT40")
      (value "TEMT6000")
      (footprint "eagle-import:TEMT6000")
      (libsource (lib "eagle-import") (part "LIGHT_SENSORTEMT6000"))
    )
    (comp (ref "PT41")
      (value "TEMT6000")
      (footprint "eagle-import:TEMT6000")
      (libsource (lib "eagle-import") (part "LIGHT_SENSORTEMT6000"))
    )
    (comp (ref "PT42")
      (value "TEMT6000")
      (footprint "eagle-import:TEMT6000")
      (libsource (lib "eagle-import") (part "LIGHT_SENSORTEMT6000"))
    )
    (comp (ref "PT43")
      (value "TEMT6000")
      (footprint "eagle-import:TEMT6000")
      (libsource (lib "eagle-import") (part "LIGHT_SENSORTEMT6000"))
    )
    (comp (ref "PT44")
      (value "TEMT6000")
      (footprint "eagle-import:TEMT6000")
      (libsource (lib "eagle-import") (part "LIGHT_SENSORTEMT6000"))
    )
    (comp (ref "PT45")
      (value "TEMT6000")
      (footprint "eagle-import:TEMT6000")
      (libsource (lib "eagle-import") (part "LIGHT_SENSORTEMT6000"))
    )
    (comp (ref "PT46")
      (value "TEMT6000")
      (footprint "eagle-import:TEMT6000")
      (libsource (lib "eagle-import") (part "LIGHT_SENSORTEMT6000"))
    )
    (comp (ref "PT47")
      (value "TEMT6000")
      (footprint "eagle-import:TEMT6000")
      (libsource (lib "eagle-import") (part "LIGHT_SENSORTEMT6000"))
    )
    (comp (ref "GND")
      (value "3,17/1,1")
      (footprint "eagle-import:3,17_1,1")
      (libsource (lib "eagle-import") (part "3,17/1,1"))
    )
    (comp (ref "J1")
      (value "CONN_13X22X13")
      (footprint "eagle-import:2X13")
      (libsource (lib "eagle-import") (part "CONN_13X22X13"))
    )
    (comp (ref "J2")
      (value "CONN_03-SCREW-5MM")
      (footprint "eagle-import:SCREWTERMINAL-5MM-3")
      (libsource (lib "eagle-import") (part "SparkFun-Connectors_513_CONN_03-SCREW-5MM"))
    )
    (comp (ref "J6")
      (value "CONN_03-SCREW-5MM")
      (footprint "eagle-import:SCREWTERMINAL-5MM-3")
      (libsource (lib "eagle-import") (part "SparkFun-Connectors_513_CONN_03-SCREW-5MM"))
    )
    (comp (ref "3C10")
      (value "22.0uF")
      (footprint "eagle-import:1210")
      (libsource (lib "eagle-import") (part "22UF-1210-16V-20%"))
    )
    (comp (ref "3C11")
      (value "22.0uF")
      (footprint "eagle-import:1210")
      (libsource (lib "eagle-import") (part "22UF-1210-16V-20%"))
    )
    (comp (ref "3C12")
      (value "10nF")
      (footprint "eagle-import:0603")
      (libsource (lib "eagle-import") (part "10NF-0603-50V-10%"))
    )
    (comp (ref "3C13")
      (value "470uF")
      (footprint "eagle-import:D_7343-31R")
      (libsource (lib "eagle-import") (part "CPOL-USD/7343-31R"))
    )
    (comp (ref "3D7")
      (value "SS54")
      (footprint "eagle-import:SMB")
      (libsource (lib "eagle-import") (part "SCHOTTKY-DIODESMD"))
    )
    (comp (ref "3L3")
      (value "XAL6060/10uH")
      (footprint "eagle-import:XAL6060")
      (libsource (lib "eagle-import") (part "XAL6060"))
    )
    (comp (ref "3R11")
      (value "10k")
      (footprint "eagle-import:0603")
      (libsource (lib "eagle-import") (part "10KOHM-0603-1/10W-1%"))
    )
    (comp (ref "3R12")
      (value "5.9k")
      (footprint "eagle-import:0603")
      (libsource (lib "eagle-import") (part "5.62KOHM-0603-1/10W-1%"))
    )
    (comp (ref "4U2")
      (value "3.1v")
      (footprint "eagle-import:POWERPAD-SOIC-8")
      (libsource (lib "eagle-import") (part "TPS5450"))
    )
  )
  (nets
    (net (code "1") (name "3.3V") (class "Default")
      (node (ref "1C1") (pin "2") (pinfunction "2_2") (pintype "passive"))
      (node (ref "1C10") (pin "1") (pinfunction "1_1") (pintype "passive"))
      (node (ref "1C2") (pin "2") (pinfunction "2_2") (pintype "passive"))
      (node (ref "1C3") (pin "2") (pinfunction "2_2") (pintype "passive"))
      (node (ref "1C4") (pin "1") (pinfunction "1_1") (pintype "passive"))
      (node (ref "1C5") (pin "1") (pinfunction "1_1") (pintype "passive"))
      (node (ref "1C6") (pin "1") (pinfunction "1_1") (pintype "passive"))
      (node (ref "1C7") (pin "1") (pinfunction "1_1") (pintype "passive"))
      (node (ref "1C8") (pin "1") (pinfunction "1_1") (pintype "passive"))
      (node (ref "1C9") (pin "1") (pinfunction "1_1") (pintype "passive"))
      (node (ref "1R10") (pin "2") (pinfunction "2_2") (pintype "passive"))
      (node (ref "1U1") (pin "P3") (pinfunction "P$V+_P3") (pintype "bidirectional"))
      (node (ref "1U2") (pin "P24") (pinfunction "VCC_P24") (pintype "bidirectional"))
      (node (ref "1U3") (pin "P24") (pinfunction "VCC_P24") (pintype "bidirectional"))
      (node (ref "1U4") (pin "P24") (pinfunction "VCC_P24") (pintype "bidirectional"))
      (node (ref "3C13") (pin "+") (pinfunction "+_+") (pintype "passive"))
      (node (ref "3L3") (pin "2") (pinfunction "2_2") (pintype "passive"))
      (node (ref "3R11") (pin "2") (pinfunction "2_2") (pintype "passive"))
      (node (ref "IRIN1") (pin "3") (pinfunction "3_3") (pintype "passive"))
      (node (ref "IRIN2") (pin "3") (pinfunction "3_3") (pintype "passive"))
      (node (ref "J1") (pin "23") (pinfunction "23_23") (pintype "passive"))
      (node (ref "LED0") (pin "A") (pinfunction "A_A") (pintype "passive"))
      (node (ref "LED1") (pin "A") (pinfunction "A_A") (pintype "passive"))
      (node (ref "LED10") (pin "A") (pinfunction "A_A") (pintype "passive"))
      (node (ref "LED11") (pin "A") (pinfunction "A_A") (pintype "passive"))
      (node (ref "LED12") (pin "A") (pinfunction "A_A") (pintype "passive"))
      (node (ref "LED13") (pin "A") (pinfunction "A_A") (pintype "passive"))
      (node (ref "LED14") (pin "A") (pinfunction "A_A") (pintype "passive"))
      (node (ref "LED15") (pin "A") (pinfunction "A_A") (pintype "passive"))
      (node (ref "LED16") (pin "A") (pinfunction "A_A") (pintype "passive"))
      (node (ref "LED17") (pin "A") (pinfunction "A_A") (pintype "passive"))
      (node (ref "LED18") (pin "A") (pinfunction "A_A") (pintype "passive"))
      (node (ref "LED19") (pin "A") (pinfunction "A_A") (pintype "passive"))
      (node (ref "LED2") (pin "A") (pinfunction "A_A") (pintype "passive"))
      (node (ref "LED20") (pin "A") (pinfunction "A_A") (pintype "passive"))
      (node (ref "LED21") (pin "A") (pinfunction "A_A") (pintype "passive"))
      (node (ref "LED22") (pin "A") (pinfunction "A_A") (pintype "passive"))
      (node (ref "LED23") (pin "A") (pinfunction "A_A") (pintype "passive"))
      (node (ref "LED24") (pin "A") (pinfunction "A_A") (pintype "passive"))
      (node (ref "LED25") (pin "A") (pinfunction "A_A") (pintype "passive"))
      (node (ref "LED26") (pin "A") (pinfunction "A_A") (pintype "passive"))
      (node (ref "LED27") (pin "A") (pinfunction "A_A") (pintype "passive"))
      (node (ref "LED28") (pin "A") (pinfunction "A_A") (pintype "passive"))
      (node (ref "LED29") (pin "A") (pinfunction "A_A") (pintype "passive"))
      (node (ref "LED3") (pin "A") (pinfunction "A_A") (pintype "passive"))
      (node (ref "LED30") (pin "A") (pinfunction "A_A") (pintype "passive"))
      (node (ref "LED31") (pin "A") (pinfunction "A_A") (pintype "passive"))
      (node (ref "LED32") (pin "A") (pinfunction "A_A") (pintype "passive"))
      (node (ref "LED33") (pin "A") (pinfunction "A_A") (pintype "passive"))
      (node (ref "LED34") (pin "A") (pinfunction "A_A") (pintype "passive"))
      (node (ref "LED35") (pin "A") (pinfunction "A_A") (pintype "passive"))
      (node (ref "LED36") (pin "A") (pinfunction "A_A") (pintype "passive"))
      (node (ref "LED37") (pin "A") (pinfunction "A_A") (pintype "passive"))
      (node (ref "LED38") (pin "A") (pinfunction "A_A") (pintype "passive"))
      (node (ref "LED39") (pin "A") (pinfunction "A_A") (pintype "passive"))
      (node (ref "LED4") (pin "A") (pinfunction "A_A") (pintype "passive"))
      (node (ref "LED40") (pin "A") (pinfunction "A_A") (pintype "passive"))
      (node (ref "LED41") (pin "A") (pinfunction "A_A") (pintype "passive"))
      (node (ref "LED42") (pin "A") (pinfunction "A_A") (pintype "passive"))
      (node (ref "LED43") (pin "A") (pinfunction "A_A") (pintype "passive"))
      (node (ref "LED44") (pin "A") (pinfunction "A_A") (pintype "passive"))
      (node (ref "LED45") (pin "A") (pinfunction "A_A") (pintype "passive"))
      (node (ref "LED46") (pin "A") (pinfunction "A_A") (pintype "passive"))
      (node (ref "LED47") (pin "A") (pinfunction "A_A") (pintype "passive"))
      (node (ref "LED48") (pin "3") (pinfunction "3_3") (pintype "passive"))
      (node (ref "LED49") (pin "3") (pinfunction "3_3") (pintype "passive"))
      (node (ref "LED5") (pin "A") (pinfunction "A_A") (pintype "passive"))
      (node (ref "LED6") (pin "A") (pinfunction "A_A") (pintype "passive"))
      (node (ref "LED7") (pin "A") (pinfunction "A_A") (pintype "passive"))
      (node (ref "LED8") (pin "A") (pinfunction "A_A") (pintype "passive"))
      (node (ref "LED9") (pin "A") (pinfunction "A_A") (pintype "passive"))
      (node (ref "PT0") (pin "COLLECTOR") (pinfunction "C1_COLLECTOR") (pintype "passive"))
      (node (ref "PT1") (pin "COLLECTOR") (pinfunction "C1_COLLECTOR") (pintype "passive"))
      (node (ref "PT10") (pin "COLLECTOR") (pinfunction "C1_COLLECTOR") (pintype "passive"))
      (node (ref "PT11") (pin "COLLECTOR") (pinfunction "C1_COLLECTOR") (pintype "passive"))
      (node (ref "PT12") (pin "COLLECTOR") (pinfunction "C1_COLLECTOR") (pintype "passive"))
      (node (ref "PT13") (pin "COLLECTOR") (pinfunction "C1_COLLECTOR") (pintype "passive"))
      (node (ref "PT14") (pin "COLLECTOR") (pinfunction "C1_COLLECTOR") (pintype "passive"))
      (node (ref "PT15") (pin "COLLECTOR") (pinfunction "C1_COLLECTOR") (pintype "passive"))
      (node (ref "PT16") (pin "COLLECTOR") (pinfunction "C1_COLLECTOR") (pintype "passive"))
      (node (ref "PT17") (pin "COLLECTOR") (pinfunction "C1_COLLECTOR") (pintype "passive"))
      (node (ref "PT18") (pin "COLLECTOR") (pinfunction "C1_COLLECTOR") (pintype "passive"))
      (node (ref "PT19") (pin "COLLECTOR") (pinfunction "C1_COLLECTOR") (pintype "passive"))
      (node (ref "PT2") (pin "COLLECTOR") (pinfunction "C1_COLLECTOR") (pintype "passive"))
      (node (ref "PT20") (pin "COLLECTOR") (pinfunction "C1_COLLECTOR") (pintype "passive"))
      (node (ref "PT21") (pin "COLLECTOR") (pinfunction "C1_COLLECTOR") (pintype "passive"))
      (node (ref "PT22") (pin "COLLECTOR") (pinfunction "C1_COLLECTOR") (pintype "passive"))
      (node (ref "PT23") (pin "COLLECTOR") (pinfunction "C1_COLLECTOR") (pintype "passive"))
      (node (ref "PT24") (pin "COLLECTOR") (pinfunction "C1_COLLECTOR") (pintype "passive"))
      (node (ref "PT25") (pin "COLLECTOR") (pinfunction "C1_COLLECTOR") (pintype "passive"))
      (node (ref "PT26") (pin "COLLECTOR") (pinfunction "C1_COLLECTOR") (pintype "passive"))
      (node (ref "PT27") (pin "COLLECTOR") (pinfunction "C1_COLLECTOR") (pintype "passive"))
      (node (ref "PT28") (pin "COLLECTOR") (pinfunction "C1_COLLECTOR") (pintype "passive"))
      (node (ref "PT29") (pin "COLLECTOR") (pinfunction "C1_COLLECTOR") (pintype "passive"))
      (node (ref "PT3") (pin "COLLECTOR") (pinfunction "C1_COLLECTOR") (pintype "passive"))
      (node (ref "PT30") (pin "COLLECTOR") (pinfunction "C1_COLLECTOR") (pintype "passive"))
      (node (ref "PT31") (pin "COLLECTOR") (pinfunction "C1_COLLECTOR") (pintype "passive"))
      (node (ref "PT32") (pin "COLLECTOR") (pinfunction "C1_COLLECTOR") (pintype "passive"))
      (node (ref "PT33") (pin "COLLECTOR") (pinfunction "C1_COLLECTOR") (pintype "passive"))
      (node (ref "PT34") (pin "COLLECTOR") (pinfunction "C1_COLLECTOR") (pintype "passive"))
      (node (ref "PT35") (pin "COLLECTOR") (pinfunction "C1_COLLECTOR") (pintype "passive"))
      (node (ref "PT36") (pin "COLLECTOR") (pinfunction "C1_COLLECTOR") (pintype "passive"))
      (node (ref "PT37") (pin "COLLECTOR") (pinfunction "C1_COLLECTOR") (pintype "passive"))
      (node (ref "PT38") (pin "COLLECTOR") (pinfunction "C1_COLLECTOR") (pintype "passive"))
      (node (ref "PT39") (pin "COLLECTOR") (pinfunction "C1_COLLECTOR") (pintype "passive"))
      (node (ref "PT4") (pin "COLLECTOR") (pinfunction "C1_COLLECTOR") (pintype "passive"))
      (node (ref "PT40") (pin "COLLECTOR") (pinfunction "C1_COLLECTOR") (pintype "passive"))
      (node (ref "PT41") (pin "COLLECTOR") (pinfunction "C1_COLLECTOR") (pintype "passive"))
      (node (ref "PT42") (pin "COLLECTOR") (pinfunction "C1_COLLECTOR") (pintype "passive"))
      (node (ref "PT43") (pin "COLLECTOR") (pinfunction "C1_COLLECTOR") (pintype "passive"))
      (node (ref "PT44") (pin "COLLECTOR") (pinfunction "C1_COLLECTOR") (pintype "passive"))
      (node (ref "PT45") (pin "COLLECTOR") (pinfunction "C1_COLLECTOR") (pintype "passive"))
      (node (ref "PT46") (pin "COLLECTOR") (pinfunction "C1_COLLECTOR") (pintype "passive"))
      (node (ref "PT47") (pin "COLLECTOR") (pinfunction "C1_COLLECTOR") (pintype "passive"))
      (node (ref "PT5") (pin "COLLECTOR") (pinfunction "C1_COLLECTOR") (pintype "passive"))
      (node (ref "PT6") (pin "COLLECTOR") (pinfunction "C1_COLLECTOR") (pintype "passive"))
      (node (ref "PT7") (pin "COLLECTOR") (pinfunction "C1_COLLECTOR") (pintype "passive"))
      (node (ref "PT8") (pin "COLLECTOR") (pinfunction "C1_COLLECTOR") (pintype "passive"))
      (node (ref "PT9") (pin "COLLECTOR") (pinfunction "C1_COLLECTOR") (pintype "passive"))
      (node (ref "R1M1") (pin "2") (pinfunction "2_2") (pintype "passive"))
      (node (ref "R1M2") (pin "2") (pinfunction "2_2") (pintype "passive"))
      (node (ref "R1M3") (pin "2") (pinfunction "2_2") (pintype "passive"))
      (node (ref "R1M4") (pin "2") (pinfunction "2_2") (pintype "passive"))
      (node (ref "R2M1") (pin "2") (pinfunction "2_2") (pintype "passive"))
      (node (ref "R2M2") (pin "2") (pinfunction "2_2") (pintype "passive"))
      (node (ref "R2M3") (pin "2") (pinfunction "2_2") (pintype "passive"))
      (node (ref "R2M4") (pin "2") (pinfunction "2_2") (pintype "passive"))
    )
    (net (code "2") (name "12V") (class "Default")
      (node (ref "3C10") (pin "1") (pinfunction "1_1") (pintype "passive"))
      (node (ref "3C11") (pin "1") (pinfunction "1_1") (pintype "passive"))
      (node (ref "4U2") (pin "7") (pinfunction "VIN_7") (pintype "power_in"))
      (node (ref "J2") (pin "3") (pinfunction "3_3") (pintype "passive"))
      (node (ref "J6") (pin "1") (pinfunction "1_1") (pintype "passive"))
    )
    (net (code "3") (name "ANALOG1") (class "Default")
      (node (ref "1JP2") (pin "3") (pinfunction "3_3") (pintype "passive"))
      (node (ref "1R2") (pin "2") (pinfunction "2_2") (pintype "passive"))
      (node (ref "1U1") (pin "P5") (pinfunction "+IN_P5") (pintype "input"))
      (node (ref "1U2") (pin "P1") (pinfunction "COM_P1") (pintype "bidirectional"))
    )
    (net (code "4") (name "ANALOG2") (class "Default")
      (node (ref "1JP4") (pin "3") (pinfunction "3_3") (pintype "passive"))
      (node (ref "1R5") (pin "2") (pinfunction "2_2") (pintype "passive"))
      (node (ref "1U1") (pin "P7") (pinfunction "+IN_P7") (pintype "input"))
      (node (ref "1U3") (pin "P1") (pinfunction "COM_P1") (pintype "bidirectional"))
    )
    (net (code "5") (name "ANALOG3") (class "Default")
      (node (ref "1JP6") (pin "3") (pinfunction "3_3") (pintype "passive"))
      (node (ref "1R8") (pin "2") (pinfunction "2_2") (pintype "passive"))
      (node (ref "1U1") (pin "P9") (pinfunction "+IN_P9") (pintype "input"))
      (node (ref "1U4") (pin "P1") (pinfunction "COM_P1") (pintype "bidirectional"))
    )
    (net (code "6") (name "COMP-") (class "Default")
      (node (ref "1R10") (pin "1") (pinfunction "1_1") (pintype "passive"))
      (node (ref "1R11") (pin "2") (pinfunction "2_2") (pintype "passive"))
      (node (ref "1U1") (pin "P4") (pinfunction "-IN_P4") (pintype "input"))
      (node (ref "1U1") (pin "P6") (pinfunction "-IN_P6") (pintype "input"))
      (node (ref "1U1") (pin "P8") (pinfunction "-IN_P8") (pintype "input"))
    )
    (net (code "7") (name "COMP1") (class "Default")
      (node (ref "1JP2") (pin "1") (pinfunction "1_1") (pintype "passive"))
      (node (ref "1U1") (pin "P2") (pinfunction "OUT_P2") (pintype "output"))
    )
    (net (code "8") (name "COMP2") (class "Default")
      (node (ref "1JP4") (pin "1") (pinfunction "1_1") (pintype "passive"))
      (node (ref "1U1") (pin "P1") (pinfunction "OUT_P1") (pintype "output"))
    )
    (net (code "9") (name "COMP3") (class "Default")
      (node (ref "1JP6") (pin "1") (pinfunction "1_1") (pintype "passive"))
      (node (ref "1U1") (pin "P14") (pinfunction "OUT_P14") (pintype "output"))
    )
    (net (code "10") (name "CPM1") (class "Default")
      (node (ref "Q1M1") (pin "1") (pinfunction "G_1") (pintype "bidirectional"))
      (node (ref "U1M1") (pin "P11") (pinfunction "CP_P11") (pintype "output"))
    )
    (net (code "11") (name "CPM2") (class "Default")
      (node (ref "Q1M2") (pin "1") (pinfunction "G_1") (pintype "bidirectional"))
      (node (ref "U1M2") (pin "P11") (pinfunction "CP_P11") (pintype "output"))
    )
    (net (code "12") (name "CPM3") (class "Default")
      (node (ref "Q1M3") (pin "1") (pinfunction "G_1") (pintype "bidirectional"))
      (node (ref "U1M3") (pin "P11") (pinfunction "CP_P11") (pintype "output"))
    )
    (net (code "13") (name "CPM4") (class "Default")
      (node (ref "Q1M4") (pin "1") (pinfunction "G_1") (pintype "bidirectional"))
      (node (ref "U1M4") (pin "P11") (pinfunction "CP_P11") (pintype "output"))
    )
    (net (code "14") (name "CSDIS1") (class "Default")
      (node (ref "R9M1") (pin "1") (pinfunction "1_1") (pintype "passive"))
      (node (ref "U1M1") (pin "P6") (pinfunction "CS_DIS_P6") (pintype "input"))
    )
    (net (code "15") (name "CSDIS2") (class "Default")
      (node (ref "R9M2") (pin "1") (pinfunction "1_1") (pintype "passive"))
      (node (ref "U1M2") (pin "P6") (pinfunction "CS_DIS_P6") (pintype "input"))
    )
    (net (code "16") (name "CSDIS3") (class "Default")
      (node (ref "R9M3") (pin "1") (pinfunction "1_1") (pintype "passive"))
      (node (ref "U1M3") (pin "P6") (pinfunction "CS_DIS_P6") (pintype "input"))
    )
    (net (code "17") (name "CSDIS4") (class "Default")
      (node (ref "R9M4") (pin "1") (pinfunction "1_1") (pintype "passive"))
      (node (ref "U1M4") (pin "P6") (pinfunction "CS_DIS_P6") (pintype "input"))
    )
    (net (code "18") (name "CSM1") (class "Default")
      (node (ref "C1M1") (pin "2") (pinfunction "2_2") (pintype "passive"))
      (node (ref "J1") (pin "15") (pinfunction "15_15") (pintype "passive"))
      (node (ref "R8M1") (pin "1") (pinfunction "1_1") (pintype "passive"))
    )
    (net (code "19") (name "CSM2") (class "Default")
      (node (ref "C1M2") (pin "2") (pinfunction "2_2") (pintype "passive"))
      (node (ref "J1") (pin "17") (pinfunction "17_17") (pintype "passive"))
      (node (ref "R8M2") (pin "1") (pinfunction "1_1") (pintype "passive"))
    )
    (net (code "20") (name "CSM3") (class "Default")
      (node (ref "C1M3") (pin "2") (pinfunction "2_2") (pintype "passive"))
      (node (ref "J1") (pin "19") (pinfunction "19_19") (pintype "passive"))
      (node (ref "R8M3") (pin "1") (pinfunction "1_1") (pintype "passive"))
    )
    (net (code "21") (name "CSM4") (class "Default")
      (node (ref "C1M4") (pin "2") (pinfunction "2_2") (pintype "passive"))
      (node (ref "J1") (pin "21") (pinfunction "21_21") (pintype "passive"))
      (node (ref "R8M4") (pin "1") (pinfunction "1_1") (pintype "passive"))
    )
    (net (code "22") (name "ENAM1") (class "Default")
      (node (ref "R3M1") (pin "1") (pinfunction "1_1") (pintype "passive"))
    )
    (net (code "23") (name "ENAM2") (class "Default")
      (node (ref "R3M2") (pin "1") (pinfunction "1_1") (pintype "passive"))
    )
    (net (code "24") (name "ENAM3") (class "Default")
      (node (ref "R3M3") (pin "1") (pinfunction "1_1") (pintype "passive"))
    )
    (net (code "25") (name "ENAM4") (class "Default")
      (node (ref "R3M4") (pin "1") (pinfunction "1_1") (pintype "passive"))
    )
    (net (code "26") (name "ENBM1") (class "Default")
      (node (ref "R4M1") (pin "2") (pinfunction "2_2") (pintype "passive"))
    )
    (net (code "27") (name "ENBM2") (class "Default")
      (node (ref "R4M2") (pin "2") (pinfunction "2_2") (pintype "passive"))
    )
    (net (code "28") (name "ENBM3") (class "Default")
      (node (ref "R4M3") (pin "2") (pinfunction "2_2") (pintype "passive"))
    )
    (net (code "29") (name "ENBM4") (class "Default")
      (node (ref "R4M4") (pin "2") (pinfunction "2_2") (pintype "passive"))
    )
    (net (code "30") (name "GATE1") (class "Default")
      (node (ref "1R12") (pin "2") (pinfunction "2_2") (pintype "passive"))
      (node (ref "IRIN1") (pin "1") (pinfunction "1_1") (pintype "passive"))
      (node (ref "J1") (pin "25") (pinfunction "25_25") (pintype "passive"))
    )
    (net (code "31") (name "GATE2") (class "Default")
      (node (ref "1R13") (pin "2") (pinfunction "2_2") (pintype "passive"))
      (node (ref "IRIN2") (pin "1") (pinfunction "1_1") (pintype "passive"))
      (node (ref "J1") (pin "26") (pinfunction "26_26") (pintype "passive"))
    )
    (net (code "32") (name "GND") (class "Default")
      (node (ref "1C1") (pin "1") (pinfunction "1_1") (pintype "passive"))
      (node (ref "1C10") (pin "2") (pinfunction "2_2") (pintype "passive"))
      (node (ref "1C2") (pin "1") (pinfunction "1_1") (pintype "passive"))
      (node (ref "1C3") (pin "1") (pinfunction "1_1") (pintype "passive"))
      (node (ref "1C4") (pin "2") (pinfunction "2_2") (pintype "passive"))
      (node (ref "1C5") (pin "2") (pinfunction "2_2") (pintype "passive"))
      (node (ref "1C6") (pin "2") (pinfunction "2_2") (pintype "passive"))
      (node (ref "1C7") (pin "2") (pinfunction "2_2") (pintype "passive"))
      (node (ref "1C8") (pin "2") (pinfunction "2_2") (pintype "passive"))
      (node (ref "1C9") (pin "2") (pinfunction "2_2") (pintype "passive"))
      (node (ref "1R1") (pin "1") (pinfunction "1_1") (pintype "passive"))
      (node (ref "1R11") (pin "1") (pinfunction "1_1") (pintype "passive"))
      (node (ref "1R12") (pin "1") (pinfunction "1_1") (pintype "passive"))
      (node (ref "1R13") (pin "1") (pinfunction "1_1") (pintype "passive"))
      (node (ref "1R3") (pin "1") (pinfunction "1_1") (pintype "passive"))
      (node (ref "1R4") (pin "1") (pinfunction "1_1") (pintype "passive"))
      (node (ref "1R6") (pin "1") (pinfunction "1_1") (pintype "passive"))
      (node (ref "1R7") (pin "1") (pinfunction "1_1") (pintype "passive"))
      (node (ref "1R9") (pin "1") (pinfunction "1_1") (pintype "passive"))
      (node (ref "1U1") (pin "P12") (pinfunction "P$V-_P12") (pintype "bidirectional"))
      (node (ref "1U2") (pin "P12") (pinfunction "GND_P12") (pintype "bidirectional"))
      (node (ref "1U3") (pin "P12") (pinfunction "GND_P12") (pintype "bidirectional"))
      (node (ref "1U4") (pin "P12") (pinfunction "GND_P12") (pintype "bidirectional"))
      (node (ref "3C10") (pin "2") (pinfunction "2_2") (pintype "passive"))
      (node (ref "3C11") (pin "2") (pinfunction "2_2") (pintype "passive"))
      (node (ref "3C13") (pin "-") (pinfunction "-_-") (pintype "passive"))
      (node (ref "3D7") (pin "A") (pinfunction "A_A") (pintype "passive"))
      (node (ref "3R12") (pin "1") (pinfunction "1_1") (pintype "passive"))
      (node (ref "4U2") (pin "6") (pinfunction "GND_6") (pintype "power_in"))
      (node (ref "4U2") (pin "9") (pinfunction "GND_9") (pintype "power_in"))
      (node (ref "4U2") (pin "P$1") (pinfunction "GND_P$1") (pintype "power_in"))
      (node (ref "4U2") (pin "P$2") (pinfunction "GND_P$2") (pintype "power_in"))
      (node (ref "4U2") (pin "P$3") (pinfunction "GND_P$3") (pintype "power_in"))
      (node (ref "4U2") (pin "P$4") (pinfunction "GND_P$4") (pintype "power_in"))
      (node (ref "4U2") (pin "P$5") (pinfunction "GND_P$5") (pintype "power_in"))
      (node (ref "4U2") (pin "P$6") (pinfunction "GND_P$6") (pintype "power_in"))
      (node (ref "C1M1") (pin "1") (pinfunction "1_1") (pintype "passive"))
      (node (ref "C1M2") (pin "1") (pinfunction "1_1") (pintype "passive"))
      (node (ref "C1M3") (pin "1") (pinfunction "1_1") (pintype "passive"))
      (node (ref "C1M4") (pin "1") (pinfunction "1_1") (pintype "passive"))
      (node (ref "C2M1") (pin "-") (pinfunction "-_-") (pintype "passive"))
      (node (ref "C2M2") (pin "-") (pinfunction "-_-") (pintype "passive"))
      (node (ref "C2M3") (pin "-") (pinfunction "-_-") (pintype "passive"))
      (node (ref "C2M4") (pin "-") (pinfunction "-_-") (pintype "passive"))
      (node (ref "C3M1") (pin "2") (pinfunction "2_2") (pintype "passive"))
      (node (ref "C3M2") (pin "2") (pinfunction "2_2") (pintype "passive"))
      (node (ref "C3M3") (pin "2") (pinfunction "2_2") (pintype "passive"))
      (node (ref "C3M4") (pin "2") (pinfunction "2_2") (pintype "passive"))
      (node (ref "GND") (pin "1") (pinfunction "P_1") (pintype "passive"))
      (node (ref "J2") (pin "1") (pinfunction "1_1") (pintype "passive"))
      (node (ref "LED0") (pin "C") (pinfunction "C_C") (pintype "passive"))
      (node (ref "LED1") (pin "C") (pinfunction "C_C") (pintype "passive"))
      (node (ref "LED10") (pin "C") (pinfunction "C_C") (pintype "passive"))
      (node (ref "LED11") (pin "C") (pinfunction "C_C") (pintype "passive"))
      (node (ref "LED12") (pin "C") (pinfunction "C_C") (pintype "passive"))
      (node (ref "LED13") (pin "C") (pinfunction "C_C") (pintype "passive"))
      (node (ref "LED14") (pin "C") (pinfunction "C_C") (pintype "passive"))
      (node (ref "LED15") (pin "C") (pinfunction "C_C") (pintype "passive"))
      (node (ref "LED16") (pin "C") (pinfunction "C_C") (pintype "passive"))
      (node (ref "LED17") (pin "C") (pinfunction "C_C") (pintype "passive"))
      (node (ref "LED18") (pin "C") (pinfunction "C_C") (pintype "passive"))
      (node (ref "LED19") (pin "C") (pinfunction "C_C") (pintype "passive"))
      (node (ref "LED2") (pin "C") (pinfunction "C_C") (pintype "passive"))
      (node (ref "LED20") (pin "C") (pinfunction "C_C") (pintype "passive"))
      (node (ref "LED21") (pin "C") (pinfunction "C_C") (pintype "passive"))
      (node (ref "LED22") (pin "C") (pinfunction "C_C") (pintype "passive"))
      (node (ref "LED23") (pin "C") (pinfunction "C_C") (pintype "passive"))
      (node (ref "LED24") (pin "C") (pinfunction "C_C") (pintype "passive"))
      (node (ref "LED25") (pin "C") (pinfunction "C_C") (pintype "passive"))
      (node (ref "LED26") (pin "C") (pinfunction "C_C") (pintype "passive"))
      (node (ref "LED27") (pin "C") (pinfunction "C_C") (pintype "passive"))
      (node (ref "LED28") (pin "C") (pinfunction "C_C") (pintype "passive"))
      (node (ref "LED29") (pin "C") (pinfunction "C_C") (pintype "passive"))
      (node (ref "LED3") (pin "C") (pinfunction "C_C") (pintype "passive"))
      (node (ref "LED30") (pin "C") (pinfunction "C_C") (pintype "passive"))
      (node (ref "LED31") (pin "C") (pinfunction "C_C") (pintype "passive"))
      (node (ref "LED32") (pin "C") (pinfunction "C_C") (pintype "passive"))
      (node (ref "LED33") (pin "C") (pinfunction "C_C") (pintype "passive"))
      (node (ref "LED34") (pin "C") (pinfunction "C_C") (pintype "passive"))
      (node (ref "LED35") (pin "C") (pinfunction "C_C") (pintype "passive"))
      (node (ref "LED36") (pin "C") (pinfunction "C_C") (pintype "passive"))
      (node (ref "LED37") (pin "C") (pinfunction "C_C") (pintype "passive"))
      (node (ref "LED38") (pin "C") (pinfunction "C_C") (pintype "passive"))
      (node (ref "LED39") (pin "C") (pinfunction "C_C") (pintype "passive"))
      (node (ref "LED4") (pin "C") (pinfunction "C_C") (pintype "passive"))
      (node (ref "LED40") (pin "C") (pinfunction "C_C") (pintype "passive"))
      (node (ref "LED41") (pin "C") (pinfunction "C_C") (pintype "passive"))
      (node (ref "LED42") (pin "C") (pinfunction "C_C") (pintype "passive"))
      (node (ref "LED43") (pin "C") (pinfunction "C_C") (pintype "passive"))
      (node (ref "LED44") (pin "C") (pinfunction "C_C") (pintype "passive"))
      (node (ref "LED45") (pin "C") (pinfunction "C_C") (pintype "passive"))
      (node (ref "LED46") (pin "C") (pinfunction "C_C") (pintype "passive"))
      (node (ref "LED47") (pin "C") (pinfunction "C_C") (pintype "passive"))
      (node (ref "LED48") (pin "1") (pinfunction "1_1") (pintype "passive"))
      (node (ref "LED49") (pin "1") (pinfunction "1_1") (pintype "passive"))
      (node (ref "LED5") (pin "C") (pinfunction "C_C") (pintype "passive"))
      (node (ref "LED6") (pin "C") (pinfunction "C_C") (pintype "passive"))
      (node (ref "LED7") (pin "C") (pinfunction "C_C") (pintype "passive"))
      (node (ref "LED8") (pin "C") (pinfunction "C_C") (pintype "passive"))
      (node (ref "LED9") (pin "C") (pinfunction "C_C") (pintype "passive"))
      (node (ref "R10M1") (pin "1") (pinfunction "1_1") (pintype "passive"))
      (node (ref "R10M2") (pin "1") (pinfunction "1_1") (pintype "passive"))
      (node (ref "R10M3") (pin "1") (pinfunction "1_1") (pintype "passive"))
      (node (ref "R10M4") (pin "1") (pinfunction "1_1") (pintype "passive"))
      (node (ref "R11M1") (pin "1") (pinfunction "1_1") (pintype "passive"))
      (node (ref "R11M2") (pin "1") (pinfunction "1_1") (pintype "passive"))
      (node (ref "R11M3") (pin "1") (pinfunction "1_1") (pintype "passive"))
      (node (ref "R11M4") (pin "1") (pinfunction "1_1") (pintype "passive"))
      (node (ref "R9M1") (pin "2") (pinfunction "2_2") (pintype "passive"))
      (node (ref "R9M2") (pin "2") (pinfunction "2_2") (pintype "passive"))
      (node (ref "R9M3") (pin "2") (pinfunction "2_2") (pintype "passive"))
      (node (ref "R9M4") (pin "2") (pinfunction "2_2") (pintype "passive"))
      (node (ref "U1M1") (pin "P18") (pinfunction "GND_P18") (pintype "output"))
      (node (ref "U1M1") (pin "P19") (pinfunction "GND_P19") (pintype "output"))
      (node (ref "U1M1") (pin "P20") (pinfunction "GND_P20") (pintype "output"))
      (node (ref "U1M1") (pin "P26") (pinfunction "GND_P26") (pintype "output"))
      (node (ref "U1M1") (pin "P27") (pinfunction "GND_P27") (pintype "output"))
      (node (ref "U1M1") (pin "P28") (pinfunction "GND_P28") (pintype "output"))
      (node (ref "U1M2") (pin "P18") (pinfunction "GND_P18") (pintype "output"))
      (node (ref "U1M2") (pin "P19") (pinfunction "GND_P19") (pintype "output"))
      (node (ref "U1M2") (pin "P20") (pinfunction "GND_P20") (pintype "output"))
      (node (ref "U1M2") (pin "P26") (pinfunction "GND_P26") (pintype "output"))
      (node (ref "U1M2") (pin "P27") (pinfunction "GND_P27") (pintype "output"))
      (node (ref "U1M2") (pin "P28") (pinfunction "GND_P28") (pintype "output"))
      (node (ref "U1M3") (pin "P18") (pinfunction "GND_P18") (pintype "output"))
      (node (ref "U1M3") (pin "P19") (pinfunction "GND_P19") (pintype "output"))
      (node (ref "U1M3") (pin "P20") (pinfunction "GND_P20") (pintype "output"))
      (node (ref "U1M3") (pin "P26") (pinfunction "GND_P26") (pintype "output"))
      (node (ref "U1M3") (pin "P27") (pinfunction "GND_P27") (pintype "output"))
      (node (ref "U1M3") (pin "P28") (pinfunction "GND_P28") (pintype "output"))
      (node (ref "U1M4") (pin "P18") (pinfunction "GND_P18") (pintype "output"))
      (node (ref "U1M4") (pin "P19") (pinfunction "GND_P19") (pintype "output"))
      (node (ref "U1M4") (pin "P20") (pinfunction "GND_P20") (pintype "output"))
      (node (ref "U1M4") (pin "P26") (pinfunction "GND_P26") (pintype "output"))
      (node (ref "U1M4") (pin "P27") (pinfunction "GND_P27") (pintype "output"))
      (node (ref "U1M4") (pin "P28") (pinfunction "GND_P28") (pintype "output"))
    )
    (net (code "33") (name "INAM1") (class "Default")
      (node (ref "J1") (pin "2") (pinfunction "2_2") (pintype "passive"))
      (node (ref "R5M1") (pin "1") (pinfunction "1_1") (pintype "passive"))
    )
    (net (code "34") (name "INAM2") (class "Default")
      (node (ref "J1") (pin "8") (pinfunction "8_8") (pintype "passive"))
      (node (ref "R5M2") (pin "1") (pinfunction "1_1") (pintype "passive"))
    )
    (net (code "35") (name "INAM3") (class "Default")
      (node (ref "J1") (pin "14") (pinfunction "14_14") (pintype "passive"))
      (node (ref "R5M3") (pin "1") (pinfunction "1_1") (pintype "passive"))
    )
    (net (code "36") (name "INAM4") (class "Default")
      (node (ref "J1") (pin "20") (pinfunction "20_20") (pintype "passive"))
      (node (ref "R5M4") (pin "1") (pinfunction "1_1") (pintype "passive"))
    )
    (net (code "37") (name "INBM1") (class "Default")
      (node (ref "J1") (pin "4") (pinfunction "4_4") (pintype "passive"))
      (node (ref "R6M1") (pin "2") (pinfunction "2_2") (pintype "passive"))
    )
    (net (code "38") (name "INBM2") (class "Default")
      (node (ref "J1") (pin "10") (pinfunction "10_10") (pintype "passive"))
      (node (ref "R6M2") (pin "2") (pinfunction "2_2") (pintype "passive"))
    )
    (net (code "39") (name "INBM3") (class "Default")
      (node (ref "J1") (pin "16") (pinfunction "16_16") (pintype "passive"))
      (node (ref "R6M3") (pin "2") (pinfunction "2_2") (pintype "passive"))
    )
    (net (code "40") (name "INBM4") (class "Default")
      (node (ref "J1") (pin "22") (pinfunction "22_22") (pintype "passive"))
      (node (ref "R6M4") (pin "2") (pinfunction "2_2") (pintype "passive"))
    )
    (net (code "41") (name "LSOUT1") (class "Default")
      (node (ref "1JP2") (pin "2") (pinfunction "2_2") (pintype "passive"))
      (node (ref "J1") (pin "9") (pinfunction "9_9") (pintype "passive"))
    )
    (net (code "42") (name "LSOUT2") (class "Default")
      (node (ref "1JP4") (pin "2") (pinfunction "2_2") (pintype "passive"))
      (node (ref "J1") (pin "11") (pinfunction "11_11") (pintype "passive"))
    )
    (net (code "43") (name "LSOUT3") (class "Default")
      (node (ref "1JP6") (pin "2") (pinfunction "2_2") (pintype "passive"))
      (node (ref "J1") (pin "13") (pinfunction "13_13") (pintype "passive"))
    )
    (net (code "44") (name "Net-(1R2-Pad1)") (class "Default")
      (node (ref "1R2") (pin "1") (pinfunction "1_1") (pintype "passive"))
      (node (ref "1R3") (pin "2") (pinfunction "2_2") (pintype "passive"))
    )
    (net (code "45") (name "Net-(1R5-Pad1)") (class "Default")
      (node (ref "1R5") (pin "1") (pinfunction "1_1") (pintype "passive"))
      (node (ref "1R6") (pin "2") (pinfunction "2_2") (pintype "passive"))
    )
    (net (code "46") (name "Net-(1R8-Pad1)") (class "Default")
      (node (ref "1R8") (pin "1") (pinfunction "1_1") (pintype "passive"))
      (node (ref "1R9") (pin "2") (pinfunction "2_2") (pintype "passive"))
    )
    (net (code "47") (name "Net-(1U2-CHAN0)") (class "Default")
      (node (ref "1U2") (pin "P9") (pinfunction "CHAN0_P9") (pintype "bidirectional"))
      (node (ref "PT0") (pin "EMITTER") (pinfunction "E1_EMITTER") (pintype "passive"))
    )
    (net (code "48") (name "Net-(1U2-CHAN1)") (class "Default")
      (node (ref "1U2") (pin "P8") (pinfunction "CHAN1_P8") (pintype "bidirectional"))
      (node (ref "PT1") (pin "EMITTER") (pinfunction "E1_EMITTER") (pintype "passive"))
    )
    (net (code "49") (name "Net-(1U2-CHAN2)") (class "Default")
      (node (ref "1U2") (pin "P7") (pinfunction "CHAN2_P7") (pintype "bidirectional"))
      (node (ref "PT2") (pin "EMITTER") (pinfunction "E1_EMITTER") (pintype "passive"))
    )
    (net (code "50") (name "Net-(1U2-CHAN3)") (class "Default")
      (node (ref "1U2") (pin "P6") (pinfunction "CHAN3_P6") (pintype "bidirectional"))
      (node (ref "PT3") (pin "EMITTER") (pinfunction "E1_EMITTER") (pintype "passive"))
    )
    (net (code "51") (name "Net-(1U2-CHAN4)") (class "Default")
      (node (ref "1U2") (pin "P5") (pinfunction "CHAN4_P5") (pintype "bidirectional"))
      (node (ref "PT4") (pin "EMITTER") (pinfunction "E1_EMITTER") (pintype "passive"))
    )
    (net (code "52") (name "Net-(1U2-CHAN5)") (class "Default")
      (node (ref "1U2") (pin "P4") (pinfunction "CHAN5_P4") (pintype "bidirectional"))
      (node (ref "PT5") (pin "EMITTER") (pinfunction "E1_EMITTER") (pintype "passive"))
    )
    (net (code "53") (name "Net-(1U2-CHAN6)") (class "Default")
      (node (ref "1U2") (pin "P3") (pinfunction "CHAN6_P3") (pintype "bidirectional"))
      (node (ref "PT6") (pin "EMITTER") (pinfunction "E1_EMITTER") (pintype "passive"))
    )
    (net (code "54") (name "Net-(1U2-CHAN7)") (class "Default")
      (node (ref "1U2") (pin "P2") (pinfunction "CHAN7_P2") (pintype "bidirectional"))
      (node (ref "PT7") (pin "EMITTER") (pinfunction "E1_EMITTER") (pintype "passive"))
    )
    (net (code "55") (name "Net-(1U2-CHAN8)") (class "Default")
      (node (ref "1U2") (pin "P23") (pinfunction "CHAN8_P23") (pintype "bidirectional"))
      (node (ref "PT8") (pin "EMITTER") (pinfunction "E1_EMITTER") (pintype "passive"))
    )
    (net (code "56") (name "Net-(1U2-CHAN9)") (class "Default")
      (node (ref "1U2") (pin "P22") (pinfunction "CHAN9_P22") (pintype "bidirectional"))
      (node (ref "PT9") (pin "EMITTER") (pinfunction "E1_EMITTER") (pintype "passive"))
    )
    (net (code "57") (name "Net-(1U2-CHAN10)") (class "Default")
      (node (ref "1U2") (pin "P21") (pinfunction "CHAN10_P21") (pintype "bidirectional"))
      (node (ref "PT10") (pin "EMITTER") (pinfunction "E1_EMITTER") (pintype "passive"))
    )
    (net (code "58") (name "Net-(1U2-CHAN11)") (class "Default")
      (node (ref "1U2") (pin "P20") (pinfunction "CHAN11_P20") (pintype "bidirectional"))
      (node (ref "PT11") (pin "EMITTER") (pinfunction "E1_EMITTER") (pintype "passive"))
    )
    (net (code "59") (name "Net-(1U2-CHAN12)") (class "Default")
      (node (ref "1U2") (pin "P19") (pinfunction "CHAN12_P19") (pintype "bidirectional"))
      (node (ref "PT12") (pin "EMITTER") (pinfunction "E1_EMITTER") (pintype "passive"))
    )
    (net (code "60") (name "Net-(1U2-CHAN13)") (class "Default")
      (node (ref "1U2") (pin "P18") (pinfunction "CHAN13_P18") (pintype "bidirectional"))
      (node (ref "PT13") (pin "EMITTER") (pinfunction "E1_EMITTER") (pintype "passive"))
    )
    (net (code "61") (name "Net-(1U2-CHAN14)") (class "Default")
      (node (ref "1U2") (pin "P17") (pinfunction "CHAN14_P17") (pintype "bidirectional"))
      (node (ref "PT14") (pin "EMITTER") (pinfunction "E1_EMITTER") (pintype "passive"))
    )
    (net (code "62") (name "Net-(1U2-CHAN15)") (class "Default")
      (node (ref "1U2") (pin "P16") (pinfunction "CHAN15_P16") (pintype "bidirectional"))
      (node (ref "PT15") (pin "EMITTER") (pinfunction "E1_EMITTER") (pintype "passive"))
    )
    (net (code "63") (name "Net-(1U2-EN)") (class "Default")
      (node (ref "1R1") (pin "2") (pinfunction "2_2") (pintype "passive"))
      (node (ref "1U2") (pin "P15") (pinfunction "EN_P15") (pintype "input"))
    )
    (net (code "64") (name "Net-(1U3-CHAN0)") (class "Default")
      (node (ref "1U3") (pin "P9") (pinfunction "CHAN0_P9") (pintype "bidirectional"))
      (node (ref "PT16") (pin "EMITTER") (pinfunction "E1_EMITTER") (pintype "passive"))
    )
    (net (code "65") (name "Net-(1U3-CHAN1)") (class "Default")
      (node (ref "1U3") (pin "P8") (pinfunction "CHAN1_P8") (pintype "bidirectional"))
      (node (ref "PT17") (pin "EMITTER") (pinfunction "E1_EMITTER") (pintype "passive"))
    )
    (net (code "66") (name "Net-(1U3-CHAN2)") (class "Default")
      (node (ref "1U3") (pin "P7") (pinfunction "CHAN2_P7") (pintype "bidirectional"))
      (node (ref "PT18") (pin "EMITTER") (pinfunction "E1_EMITTER") (pintype "passive"))
    )
    (net (code "67") (name "Net-(1U3-CHAN3)") (class "Default")
      (node (ref "1U3") (pin "P6") (pinfunction "CHAN3_P6") (pintype "bidirectional"))
      (node (ref "PT19") (pin "EMITTER") (pinfunction "E1_EMITTER") (pintype "passive"))
    )
    (net (code "68") (name "Net-(1U3-CHAN4)") (class "Default")
      (node (ref "1U3") (pin "P5") (pinfunction "CHAN4_P5") (pintype "bidirectional"))
      (node (ref "PT20") (pin "EMITTER") (pinfunction "E1_EMITTER") (pintype "passive"))
    )
    (net (code "69") (name "Net-(1U3-CHAN5)") (class "Default")
      (node (ref "1U3") (pin "P4") (pinfunction "CHAN5_P4") (pintype "bidirectional"))
      (node (ref "PT21") (pin "EMITTER") (pinfunction "E1_EMITTER") (pintype "passive"))
    )
    (net (code "70") (name "Net-(1U3-CHAN6)") (class "Default")
      (node (ref "1U3") (pin "P3") (pinfunction "CHAN6_P3") (pintype "bidirectional"))
      (node (ref "PT22") (pin "EMITTER") (pinfunction "E1_EMITTER") (pintype "passive"))
    )
    (net (code "71") (name "Net-(1U3-CHAN7)") (class "Default")
      (node (ref "1U3") (pin "P2") (pinfunction "CHAN7_P2") (pintype "bidirectional"))
      (node (ref "PT23") (pin "EMITTER") (pinfunction "E1_EMITTER") (pintype "passive"))
    )
    (net (code "72") (name "Net-(1U3-CHAN8)") (class "Default")
      (node (ref "1U3") (pin "P23") (pinfunction "CHAN8_P23") (pintype "bidirectional"))
      (node (ref "PT24") (pin "EMITTER") (pinfunction "E1_EMITTER") (pintype "passive"))
    )
    (net (code "73") (name "Net-(1U3-CHAN9)") (class "Default")
      (node (ref "1U3") (pin "P22") (pinfunction "CHAN9_P22") (pintype "bidirectional"))
      (node (ref "PT25") (pin "EMITTER") (pinfunction "E1_EMITTER") (pintype "passive"))
    )
    (net (code "74") (name "Net-(1U3-CHAN10)") (class "Default")
      (node (ref "1U3") (pin "P21") (pinfunction "CHAN10_P21") (pintype "bidirectional"))
      (node (ref "PT26") (pin "EMITTER") (pinfunction "E1_EMITTER") (pintype "passive"))
    )
    (net (code "75") (name "Net-(1U3-CHAN11)") (class "Default")
      (node (ref "1U3") (pin "P20") (pinfunction "CHAN11_P20") (pintype "bidirectional"))
      (node (ref "PT27") (pin "EMITTER") (pinfunction "E1_EMITTER") (pintype "passive"))
    )
    (net (code "76") (name "Net-(1U3-CHAN12)") (class "Default")
      (node (ref "1U3") (pin "P19") (pinfunction "CHAN12_P19") (pintype "bidirectional"))
      (node (ref "PT28") (pin "EMITTER") (pinfunction "E1_EMITTER") (pintype "passive"))
    )
    (net (code "77") (name "Net-(1U3-CHAN13)") (class "Default")
      (node (ref "1U3") (pin "P18") (pinfunction "CHAN13_P18") (pintype "bidirectional"))
      (node (ref "PT29") (pin "EMITTER") (pinfunction "E1_EMITTER") (pintype "passive"))
    )
    (net (code "78") (name "Net-(1U3-CHAN14)") (class "Default")
      (node (ref "1U3") (pin "P17") (pinfunction "CHAN14_P17") (pintype "bidirectional"))
      (node (ref "PT30") (pin "EMITTER") (pinfunction "E1_EMITTER") (pintype "passive"))
    )
    (net (code "79") (name "Net-(1U3-CHAN15)") (class "Default")
      (node (ref "1U3") (pin "P16") (pinfunction "CHAN15_P16") (pintype "bidirectional"))
      (node (ref "PT31") (pin "EMITTER") (pinfunction "E1_EMITTER") (pintype "passive"))
    )
    (net (code "80") (name "Net-(1U3-EN)") (class "Default")
      (node (ref "1R4") (pin "2") (pinfunction "2_2") (pintype "passive"))
      (node (ref "1U3") (pin "P15") (pinfunction "EN_P15") (pintype "input"))
    )
    (net (code "81") (name "Net-(1U4-CHAN0)") (class "Default")
      (node (ref "1U4") (pin "P9") (pinfunction "CHAN0_P9") (pintype "bidirectional"))
      (node (ref "PT32") (pin "EMITTER") (pinfunction "E1_EMITTER") (pintype "passive"))
    )
    (net (code "82") (name "Net-(1U4-CHAN1)") (class "Default")
      (node (ref "1U4") (pin "P8") (pinfunction "CHAN1_P8") (pintype "bidirectional"))
      (node (ref "PT33") (pin "EMITTER") (pinfunction "E1_EMITTER") (pintype "passive"))
    )
    (net (code "83") (name "Net-(1U4-CHAN2)") (class "Default")
      (node (ref "1U4") (pin "P7") (pinfunction "CHAN2_P7") (pintype "bidirectional"))
      (node (ref "PT34") (pin "EMITTER") (pinfunction "E1_EMITTER") (pintype "passive"))
    )
    (net (code "84") (name "Net-(1U4-CHAN3)") (class "Default")
      (node (ref "1U4") (pin "P6") (pinfunction "CHAN3_P6") (pintype "bidirectional"))
      (node (ref "PT35") (pin "EMITTER") (pinfunction "E1_EMITTER") (pintype "passive"))
    )
    (net (code "85") (name "Net-(1U4-CHAN4)") (class "Default")
      (node (ref "1U4") (pin "P5") (pinfunction "CHAN4_P5") (pintype "bidirectional"))
      (node (ref "PT36") (pin "EMITTER") (pinfunction "E1_EMITTER") (pintype "passive"))
    )
    (net (code "86") (name "Net-(1U4-CHAN5)") (class "Default")
      (node (ref "1U4") (pin "P4") (pinfunction "CHAN5_P4") (pintype "bidirectional"))
      (node (ref "PT37") (pin "EMITTER") (pinfunction "E1_EMITTER") (pintype "passive"))
    )
    (net (code "87") (name "Net-(1U4-CHAN6)") (class "Default")
      (node (ref "1U4") (pin "P3") (pinfunction "CHAN6_P3") (pintype "bidirectional"))
      (node (ref "PT38") (pin "EMITTER") (pinfunction "E1_EMITTER") (pintype "passive"))
    )
    (net (code "88") (name "Net-(1U4-CHAN7)") (class "Default")
      (node (ref "1U4") (pin "P2") (pinfunction "CHAN7_P2") (pintype "bidirectional"))
      (node (ref "PT39") (pin "EMITTER") (pinfunction "E1_EMITTER") (pintype "passive"))
    )
    (net (code "89") (name "Net-(1U4-CHAN8)") (class "Default")
      (node (ref "1U4") (pin "P23") (pinfunction "CHAN8_P23") (pintype "bidirectional"))
      (node (ref "PT40") (pin "EMITTER") (pinfunction "E1_EMITTER") (pintype "passive"))
    )
    (net (code "90") (name "Net-(1U4-CHAN9)") (class "Default")
      (node (ref "1U4") (pin "P22") (pinfunction "CHAN9_P22") (pintype "bidirectional"))
      (node (ref "PT41") (pin "EMITTER") (pinfunction "E1_EMITTER") (pintype "passive"))
    )
    (net (code "91") (name "Net-(1U4-CHAN10)") (class "Default")
      (node (ref "1U4") (pin "P21") (pinfunction "CHAN10_P21") (pintype "bidirectional"))
      (node (ref "PT42") (pin "EMITTER") (pinfunction "E1_EMITTER") (pintype "passive"))
    )
    (net (code "92") (name "Net-(1U4-CHAN11)") (class "Default")
      (node (ref "1U4") (pin "P20") (pinfunction "CHAN11_P20") (pintype "bidirectional"))
      (node (ref "PT43") (pin "EMITTER") (pinfunction "E1_EMITTER") (pintype "passive"))
    )
    (net (code "93") (name "Net-(1U4-CHAN12)") (class "Default")
      (node (ref "1U4") (pin "P19") (pinfunction "CHAN12_P19") (pintype "bidirectional"))
      (node (ref "PT44") (pin "EMITTER") (pinfunction "E1_EMITTER") (pintype "passive"))
    )
    (net (code "94") (name "Net-(1U4-CHAN13)") (class "Default")
      (node (ref "1U4") (pin "P18") (pinfunction "CHAN13_P18") (pintype "bidirectional"))
      (node (ref "PT45") (pin "EMITTER") (pinfunction "E1_EMITTER") (pintype "passive"))
    )
    (net (code "95") (name "Net-(1U4-CHAN14)") (class "Default")
      (node (ref "1U4") (pin "P17") (pinfunction "CHAN14_P17") (pintype "bidirectional"))
      (node (ref "PT46") (pin "EMITTER") (pinfunction "E1_EMITTER") (pintype "passive"))
    )
    (net (code "96") (name "Net-(1U4-CHAN15)") (class "Default")
      (node (ref "1U4") (pin "P16") (pinfunction "CHAN15_P16") (pintype "bidirectional"))
      (node (ref "PT47") (pin "EMITTER") (pinfunction "E1_EMITTER") (pintype "passive"))
    )
    (net (code "97") (name "Net-(1U4-EN)") (class "Default")
      (node (ref "1R7") (pin "2") (pinfunction "2_2") (pintype "passive"))
      (node (ref "1U4") (pin "P15") (pinfunction "EN_P15") (pintype "input"))
    )
    (net (code "98") (name "Net-(4U2-BOOT)") (class "Default")
      (node (ref "3C12") (pin "1") (pinfunction "1_1") (pintype "passive"))
      (node (ref "4U2") (pin "1") (pinfunction "BOOT_1") (pintype "bidirectional"))
    )
    (net (code "99") (name "Net-(4U2-PH)") (class "Default")
      (node (ref "3C12") (pin "2") (pinfunction "2_2") (pintype "passive"))
      (node (ref "3D7") (pin "C") (pinfunction "C_C") (pintype "passive"))
      (node (ref "3L3") (pin "1") (pinfunction "1_1") (pintype "passive"))
      (node (ref "4U2") (pin "8") (pinfunction "PH_8") (pintype "bidirectional"))
    )
    (net (code "100") (name "Net-(4U2-VSNS)") (class "Default")
      (node (ref "3R11") (pin "1") (pinfunction "1_1") (pintype "passive"))
      (node (ref "3R12") (pin "2") (pinfunction "2_2") (pintype "passive"))
      (node (ref "4U2") (pin "4") (pinfunction "VSNS_4") (pintype "input"))
    )
    (net (code "101") (name "Net-(D1M1-PadC)") (class "Default")
      (node (ref "D1M1") (pin "C") (pinfunction "C_C") (pintype "passive"))
      (node (ref "D2M1") (pin "A") (pinfunction "A_A") (pintype "passive"))
      (node (ref "R12M1") (pin "1") (pinfunction "1_1") (pintype "passive"))
    )
    (net (code "102") (name "Net-(D1M2-PadC)") (class "Default")
      (node (ref "D1M2") (pin "C") (pinfunction "C_C") (pintype "passive"))
      (node (ref "D2M2") (pin "A") (pinfunction "A_A") (pintype "passive"))
      (node (ref "R12M2") (pin "1") (pinfunction "1_1") (pintype "passive"))
    )
    (net (code "103") (name "Net-(D1M3-PadC)") (class "Default")
      (node (ref "D1M3") (pin "C") (pinfunction "C_C") (pintype "passive"))
      (node (ref "D2M3") (pin "A") (pinfunction "A_A") (pintype "passive"))
      (node (ref "R12M3") (pin "1") (pinfunction "1_1") (pintype "passive"))
    )
    (net (code "104") (name "Net-(D1M4-PadC)") (class "Default")
      (node (ref "D1M4") (pin "C") (pinfunction "C_C") (pintype "passive"))
      (node (ref "D2M4") (pin "A") (pinfunction "A_A") (pintype "passive"))
      (node (ref "R12M4") (pin "1") (pinfunction "1_1") (pintype "passive"))
    )
    (net (code "105") (name "Net-(Q1M1-D)") (class "Default")
      (node (ref "C2M1") (pin "+") (pinfunction "+_+") (pintype "passive"))
      (node (ref "C3M1") (pin "1") (pinfunction "1_1") (pintype "passive"))
      (node (ref "Q1M1") (pin "4") (pinfunction "D_4") (pintype "bidirectional"))
      (node (ref "U1M1") (pin "P13") (pinfunction "VCC_P13") (pintype "power_in"))
      (node (ref "U1M1") (pin "P23") (pinfunction "VCC_P23") (pintype "power_in"))
      (node (ref "U1M1") (pin "P3") (pinfunction "VCC_P3") (pintype "power_in"))
      (node (ref "U1M1") (pin "SLUG1") (pinfunction "VCC_SLUG1") (pintype "power_in"))
    )
    (net (code "106") (name "Net-(Q1M2-D)") (class "Default")
      (node (ref "C2M2") (pin "+") (pinfunction "+_+") (pintype "passive"))
      (node (ref "C3M2") (pin "1") (pinfunction "1_1") (pintype "passive"))
      (node (ref "Q1M2") (pin "4") (pinfunction "D_4") (pintype "bidirectional"))
      (node (ref "U1M2") (pin "P13") (pinfunction "VCC_P13") (pintype "power_in"))
      (node (ref "U1M2") (pin "P23") (pinfunction "VCC_P23") (pintype "power_in"))
      (node (ref "U1M2") (pin "P3") (pinfunction "VCC_P3") (pintype "power_in"))
      (node (ref "U1M2") (pin "SLUG1") (pinfunction "VCC_SLUG1") (pintype "power_in"))
    )
    (net (code "107") (name "Net-(Q1M3-D)") (class "Default")
      (node (ref "C2M3") (pin "+") (pinfunction "+_+") (pintype "passive"))
      (node (ref "C3M3") (pin "1") (pinfunction "1_1") (pintype "passive"))
      (node (ref "Q1M3") (pin "4") (pinfunction "D_4") (pintype "bidirectional"))
      (node (ref "U1M3") (pin "P13") (pinfunction "VCC_P13") (pintype "power_in"))
      (node (ref "U1M3") (pin "P23") (pinfunction "VCC_P23") (pintype "power_in"))
      (node (ref "U1M3") (pin "P3") (pinfunction "VCC_P3") (pintype "power_in"))
      (node (ref "U1M3") (pin "SLUG1") (pinfunction "VCC_SLUG1") (pintype "power_in"))
    )
    (net (code "108") (name "Net-(Q1M4-D)") (class "Default")
      (node (ref "C2M4") (pin "+") (pinfunction "+_+") (pintype "passive"))
      (node (ref "C3M4") (pin "1") (pinfunction "1_1") (pintype "passive"))
      (node (ref "Q1M4") (pin "4") (pinfunction "D_4") (pintype "bidirectional"))
      (node (ref "U1M4") (pin "P13") (pinfunction "VCC_P13") (pintype "power_in"))
      (node (ref "U1M4") (pin "P23") (pinfunction "VCC_P23") (pintype "power_in"))
      (node (ref "U1M4") (pin "P3") (pinfunction "VCC_P3") (pintype "power_in"))
      (node (ref "U1M4") (pin "SLUG1") (pinfunction "VCC_SLUG1") (pintype "power_in"))
    )
    (net (code "109") (name "Net-(U1M1-CS)") (class "Default")
      (node (ref "R10M1") (pin "2") (pinfunction "2_2") (pintype "passive"))
      (node (ref "R8M1") (pin "2") (pinfunction "2_2") (pintype "passive"))
      (node (ref "U1M1") (pin "P8") (pinfunction "CS_P8") (pintype "output"))
    )
    (net (code "110") (name "Net-(U1M1-EN_A)") (class "Default")
      (node (ref "R2M1") (pin "1") (pinfunction "1_1") (pintype "passive"))
      (node (ref "R3M1") (pin "2") (pinfunction "2_2") (pintype "passive"))
      (node (ref "U1M1") (pin "P5") (pinfunction "EN_A_P5") (pintype "bidirectional"))
    )
    (net (code "111") (name "Net-(U1M1-EN_B)") (class "Default")
      (node (ref "R1M1") (pin "1") (pinfunction "1_1") (pintype "passive"))
      (node (ref "R4M1") (pin "1") (pinfunction "1_1") (pintype "passive"))
      (node (ref "U1M1") (pin "P9") (pinfunction "EN_B_P9") (pintype "bidirectional"))
    )
    (net (code "112") (name "Net-(U1M1-IN_A)") (class "Default")
      (node (ref "R5M1") (pin "2") (pinfunction "2_2") (pintype "passive"))
      (node (ref "U1M1") (pin "P4") (pinfunction "IN_A_P4") (pintype "input"))
    )
    (net (code "113") (name "Net-(U1M1-IN_B)") (class "Default")
      (node (ref "R6M1") (pin "1") (pinfunction "1_1") (pintype "passive"))
      (node (ref "U1M1") (pin "P10") (pinfunction "IN_B_P10") (pintype "input"))
    )
    (net (code "114") (name "Net-(U1M1-PWM_IN)") (class "Default")
      (node (ref "R7M1") (pin "1") (pinfunction "1_1") (pintype "passive"))
      (node (ref "U1M1") (pin "P7") (pinfunction "PWM_IN_P7") (pintype "input"))
    )
    (net (code "115") (name "Net-(U1M2-CS)") (class "Default")
      (node (ref "R10M2") (pin "2") (pinfunction "2_2") (pintype "passive"))
      (node (ref "R8M2") (pin "2") (pinfunction "2_2") (pintype "passive"))
      (node (ref "U1M2") (pin "P8") (pinfunction "CS_P8") (pintype "output"))
    )
    (net (code "116") (name "Net-(U1M2-EN_A)") (class "Default")
      (node (ref "R2M2") (pin "1") (pinfunction "1_1") (pintype "passive"))
      (node (ref "R3M2") (pin "2") (pinfunction "2_2") (pintype "passive"))
      (node (ref "U1M2") (pin "P5") (pinfunction "EN_A_P5") (pintype "bidirectional"))
    )
    (net (code "117") (name "Net-(U1M2-EN_B)") (class "Default")
      (node (ref "R1M2") (pin "1") (pinfunction "1_1") (pintype "passive"))
      (node (ref "R4M2") (pin "1") (pinfunction "1_1") (pintype "passive"))
      (node (ref "U1M2") (pin "P9") (pinfunction "EN_B_P9") (pintype "bidirectional"))
    )
    (net (code "118") (name "Net-(U1M2-IN_A)") (class "Default")
      (node (ref "R5M2") (pin "2") (pinfunction "2_2") (pintype "passive"))
      (node (ref "U1M2") (pin "P4") (pinfunction "IN_A_P4") (pintype "input"))
    )
    (net (code "119") (name "Net-(U1M2-IN_B)") (class "Default")
      (node (ref "R6M2") (pin "1") (pinfunction "1_1") (pintype "passive"))
      (node (ref "U1M2") (pin "P10") (pinfunction "IN_B_P10") (pintype "input"))
    )
    (net (code "120") (name "Net-(U1M2-PWM_IN)") (class "Default")
      (node (ref "R7M2") (pin "1") (pinfunction "1_1") (pintype "passive"))
      (node (ref "U1M2") (pin "P7") (pinfunction "PWM_IN_P7") (pintype "input"))
    )
    (net (code "121") (name "Net-(U1M3-CS)") (class "Default")
      (node (ref "R10M3") (pin "2") (pinfunction "2_2") (pintype "passive"))
      (node (ref "R8M3") (pin "2") (pinfunction "2_2") (pintype "passive"))
      (node (ref "U1M3") (pin "P8") (pinfunction "CS_P8") (pintype "output"))
    )
    (net (code "122") (name "Net-(U1M3-EN_A)") (class "Default")
      (node (ref "R2M3") (pin "1") (pinfunction "1_1") (pintype "passive"))
      (node (ref "R3M3") (pin "2") (pinfunction "2_2") (pintype "passive"))
      (node (ref "U1M3") (pin "P5") (pinfunction "EN_A_P5") (pintype "bidirectional"))
    )
    (net (code "123") (name "Net-(U1M3-EN_B)") (class "Default")
      (node (ref "R1M3") (pin "1") (pinfunction "1_1") (pintype "passive"))
      (node (ref "R4M3") (pin "1") (pinfunction "1_1") (pintype "passive"))
      (node (ref "U1M3") (pin "P9") (pinfunction "EN_B_P9") (pintype "bidirectional"))
    )
    (net (code "124") (name "Net-(U1M3-IN_A)") (class "Default")
      (node (ref "R5M3") (pin "2") (pinfunction "2_2") (pintype "passive"))
      (node (ref "U1M3") (pin "P4") (pinfunction "IN_A_P4") (pintype "input"))
    )
    (net (code "125") (name "Net-(U1M3-IN_B)") (class "Default")
      (node (ref "R6M3") (pin "1") (pinfunction "1_1") (pintype "passive"))
      (node (ref "U1M3") (pin "P10") (pinfunction "IN_B_P10") (pintype "input"))
    )
    (net (code "126") (name "Net-(U1M3-PWM_IN)") (class "Default")
      (node (ref "R7M3") (pin "1") (pinfunction "1_1") (pintype "passive"))
      (node (ref "U1M3") (pin "P7") (pinfunction "PWM_IN_P7") (pintype "input"))
    )
    (net (code "127") (name "Net-(U1M4-CS)") (class "Default")
      (node (ref "R10M4") (pin "2") (pinfunction "2_2") (pintype "passive"))
      (node (ref "R8M4") (pin "2") (pinfunction "2_2") (pintype "passive"))
      (node (ref "U1M4") (pin "P8") (pinfunction "CS_P8") (pintype "output"))
    )
    (net (code "128") (name "Net-(U1M4-EN_A)") (class "Default")
      (node (ref "R2M4") (pin "1") (pinfunction "1_1") (pintype "passive"))
      (node (ref "R3M4") (pin "2") (pinfunction "2_2") (pintype "passive"))
      (node (ref "U1M4") (pin "P5") (pinfunction "EN_A_P5") (pintype "bidirectional"))
    )
    (net (code "129") (name "Net-(U1M4-EN_B)") (class "Default")
      (node (ref "R1M4") (pin "1") (pinfunction "1_1") (pintype "passive"))
      (node (ref "R4M4") (pin "1") (pinfunction "1_1") (pintype "passive"))
      (node (ref "U1M4") (pin "P9") (pinfunction "EN_B_P9") (pintype "bidirectional"))
    )
    (net (code "130") (name "Net-(U1M4-IN_A)") (class "Default")
      (node (ref "R5M4") (pin "2") (pinfunction "2_2") (pintype "passive"))
      (node (ref "U1M4") (pin "P4") (pinfunction "IN_A_P4") (pintype "input"))
    )
    (net (code "131") (name "Net-(U1M4-IN_B)") (class "Default")
      (node (ref "R6M4") (pin "1") (pinfunction "1_1") (pintype "passive"))
      (node (ref "U1M4") (pin "P10") (pinfunction "IN_B_P10") (pintype "input"))
    )
    (net (code "132") (name "Net-(U1M4-PWM_IN)") (class "Default")
      (node (ref "R7M4") (pin "1") (pinfunction "1_1") (pintype "passive"))
      (node (ref "U1M4") (pin "P7") (pinfunction "PWM_IN_P7") (pintype "input"))
    )
    (net (code "133") (name "OUTAM1") (class "Default")
      (node (ref "D1M1") (pin "A") (pinfunction "A_A") (pintype "passive"))
      (node (ref "D2M1") (pin "C") (pinfunction "C_C") (pintype "passive"))
      (node (ref "J1M1") (pin "1") (pinfunction "1_1") (pintype "passive"))
      (node (ref "U1M1") (pin "P1") (pinfunction "OUT_A_P1") (pintype "output"))
      (node (ref "U1M1") (pin "P25") (pinfunction "OUT_A_P25") (pintype "output"))
      (node (ref "U1M1") (pin "P30") (pinfunction "OUT_A_P30") (pintype "output"))
      (node (ref "U1M1") (pin "SLUG2") (pinfunction "OUT_A_SLUG2") (pintype "output"))
    )
    (net (code "134") (name "OUTAM2") (class "Default")
      (node (ref "D1M2") (pin "A") (pinfunction "A_A") (pintype "passive"))
      (node (ref "D2M2") (pin "C") (pinfunction "C_C") (pintype "passive"))
      (node (ref "J1M2") (pin "1") (pinfunction "1_1") (pintype "passive"))
      (node (ref "U1M2") (pin "P1") (pinfunction "OUT_A_P1") (pintype "output"))
      (node (ref "U1M2") (pin "P25") (pinfunction "OUT_A_P25") (pintype "output"))
      (node (ref "U1M2") (pin "P30") (pinfunction "OUT_A_P30") (pintype "output"))
      (node (ref "U1M2") (pin "SLUG2") (pinfunction "OUT_A_SLUG2") (pintype "output"))
    )
    (net (code "135") (name "OUTAM3") (class "Default")
      (node (ref "D1M3") (pin "A") (pinfunction "A_A") (pintype "passive"))
      (node (ref "D2M3") (pin "C") (pinfunction "C_C") (pintype "passive"))
      (node (ref "J1M3") (pin "1") (pinfunction "1_1") (pintype "passive"))
      (node (ref "U1M3") (pin "P1") (pinfunction "OUT_A_P1") (pintype "output"))
      (node (ref "U1M3") (pin "P25") (pinfunction "OUT_A_P25") (pintype "output"))
      (node (ref "U1M3") (pin "P30") (pinfunction "OUT_A_P30") (pintype "output"))
      (node (ref "U1M3") (pin "SLUG2") (pinfunction "OUT_A_SLUG2") (pintype "output"))
    )
    (net (code "136") (name "OUTAM4") (class "Default")
      (node (ref "D1M4") (pin "A") (pinfunction "A_A") (pintype "passive"))
      (node (ref "D2M4") (pin "C") (pinfunction "C_C") (pintype "passive"))
      (node (ref "J1M4") (pin "1") (pinfunction "1_1") (pintype "passive"))
      (node (ref "U1M4") (pin "P1") (pinfunction "OUT_A_P1") (pintype "output"))
      (node (ref "U1M4") (pin "P25") (pinfunction "OUT_A_P25") (pintype "output"))
      (node (ref "U1M4") (pin "P30") (pinfunction "OUT_A_P30") (pintype "output"))
      (node (ref "U1M4") (pin "SLUG2") (pinfunction "OUT_A_SLUG2") (pintype "output"))
    )
    (net (code "137") (name "OUTBM1") (class "Default")
      (node (ref "J1M1") (pin "3") (pinfunction "3_3") (pintype "passive"))
      (node (ref "R12M1") (pin "2") (pinfunction "2_2") (pintype "passive"))
      (node (ref "U1M1") (pin "P15") (pinfunction "OUT_B_P15") (pintype "output"))
      (node (ref "U1M1") (pin "P16") (pinfunction "OUT_B_P16") (pintype "output"))
      (node (ref "U1M1") (pin "P21") (pinfunction "OUT_B_P21") (pintype "output"))
      (node (ref "U1M1") (pin "SLUG3") (pinfunction "OUT_B_SLUG3") (pintype "output"))
    )
    (net (code "138") (name "OUTBM2") (class "Default")
      (node (ref "J1M2") (pin "3") (pinfunction "3_3") (pintype "passive"))
      (node (ref "R12M2") (pin "2") (pinfunction "2_2") (pintype "passive"))
      (node (ref "U1M2") (pin "P15") (pinfunction "OUT_B_P15") (pintype "output"))
      (node (ref "U1M2") (pin "P16") (pinfunction "OUT_B_P16") (pintype "output"))
      (node (ref "U1M2") (pin "P21") (pinfunction "OUT_B_P21") (pintype "output"))
      (node (ref "U1M2") (pin "SLUG3") (pinfunction "OUT_B_SLUG3") (pintype "output"))
    )
    (net (code "139") (name "OUTBM3") (class "Default")
      (node (ref "J1M3") (pin "3") (pinfunction "3_3") (pintype "passive"))
      (node (ref "R12M3") (pin "2") (pinfunction "2_2") (pintype "passive"))
      (node (ref "U1M3") (pin "P15") (pinfunction "OUT_B_P15") (pintype "output"))
      (node (ref "U1M3") (pin "P16") (pinfunction "OUT_B_P16") (pintype "output"))
      (node (ref "U1M3") (pin "P21") (pinfunction "OUT_B_P21") (pintype "output"))
      (node (ref "U1M3") (pin "SLUG3") (pinfunction "OUT_B_SLUG3") (pintype "output"))
    )
    (net (code "140") (name "OUTBM4") (class "Default")
      (node (ref "J1M4") (pin "3") (pinfunction "3_3") (pintype "passive"))
      (node (ref "R12M4") (pin "2") (pinfunction "2_2") (pintype "passive"))
      (node (ref "U1M4") (pin "P15") (pinfunction "OUT_B_P15") (pintype "output"))
      (node (ref "U1M4") (pin "P16") (pinfunction "OUT_B_P16") (pintype "output"))
      (node (ref "U1M4") (pin "P21") (pinfunction "OUT_B_P21") (pintype "output"))
      (node (ref "U1M4") (pin "SLUG3") (pinfunction "OUT_B_SLUG3") (pintype "output"))
    )
    (net (code "141") (name "PWMM1") (class "Default")
      (node (ref "J1") (pin "6") (pinfunction "6_6") (pintype "passive"))
      (node (ref "R11M1") (pin "2") (pinfunction "2_2") (pintype "passive"))
      (node (ref "R7M1") (pin "2") (pinfunction "2_2") (pintype "passive"))
    )
    (net (code "142") (name "PWMM2") (class "Default")
      (node (ref "J1") (pin "12") (pinfunction "12_12") (pintype "passive"))
      (node (ref "R11M2") (pin "2") (pinfunction "2_2") (pintype "passive"))
      (node (ref "R7M2") (pin "2") (pinfunction "2_2") (pintype "passive"))
    )
    (net (code "143") (name "PWMM3") (class "Default")
      (node (ref "J1") (pin "18") (pinfunction "18_18") (pintype "passive"))
      (node (ref "R11M3") (pin "2") (pinfunction "2_2") (pintype "passive"))
      (node (ref "R7M3") (pin "2") (pinfunction "2_2") (pintype "passive"))
    )
    (net (code "144") (name "PWMM4") (class "Default")
      (node (ref "J1") (pin "24") (pinfunction "24_24") (pintype "passive"))
      (node (ref "R11M4") (pin "2") (pinfunction "2_2") (pintype "passive"))
      (node (ref "R7M4") (pin "2") (pinfunction "2_2") (pintype "passive"))
    )
    (net (code "145") (name "S0") (class "Default")
      (node (ref "1U2") (pin "P10") (pinfunction "S0_P10") (pintype "input"))
      (node (ref "1U3") (pin "P10") (pinfunction "S0_P10") (pintype "input"))
      (node (ref "1U4") (pin "P10") (pinfunction "S0_P10") (pintype "input"))
      (node (ref "J1") (pin "1") (pinfunction "1_1") (pintype "passive"))
    )
    (net (code "146") (name "S1") (class "Default")
      (node (ref "1U2") (pin "P11") (pinfunction "S1_P11") (pintype "input"))
      (node (ref "1U3") (pin "P11") (pinfunction "S1_P11") (pintype "input"))
      (node (ref "1U4") (pin "P11") (pinfunction "S1_P11") (pintype "input"))
      (node (ref "J1") (pin "3") (pinfunction "3_3") (pintype "passive"))
    )
    (net (code "147") (name "S2") (class "Default")
      (node (ref "1U2") (pin "P14") (pinfunction "S2_P14") (pintype "input"))
      (node (ref "1U3") (pin "P14") (pinfunction "S2_P14") (pintype "input"))
      (node (ref "1U4") (pin "P14") (pinfunction "S2_P14") (pintype "input"))
      (node (ref "J1") (pin "5") (pinfunction "5_5") (pintype "passive"))
    )
    (net (code "148") (name "S3") (class "Default")
      (node (ref "1U2") (pin "P13") (pinfunction "S3_P13") (pintype "input"))
      (node (ref "1U3") (pin "P13") (pinfunction "S3_P13") (pintype "input"))
      (node (ref "1U4") (pin "P13") (pinfunction "S3_P13") (pintype "input"))
      (node (ref "J1") (pin "7") (pinfunction "7_7") (pintype "passive"))
    )
    (net (code "149") (name "VCC_1") (class "Default")
      (node (ref "J6") (pin "3") (pinfunction "3_3") (pintype "passive"))
      (node (ref "Q1M1") (pin "3") (pinfunction "S_3") (pintype "bidirectional"))
      (node (ref "Q1M2") (pin "3") (pinfunction "S_3") (pintype "bidirectional"))
      (node (ref "Q1M3") (pin "3") (pinfunction "S_3") (pintype "bidirectional"))
      (node (ref "Q1M4") (pin "3") (pinfunction "S_3") (pintype "bidirectional"))
      (node (ref "U1M1") (pin "P12") (pinfunction "VBAT_P12") (pintype "power_in"))
      (node (ref "U1M2") (pin "P12") (pinfunction "VBAT_P12") (pintype "power_in"))
      (node (ref "U1M3") (pin "P12") (pinfunction "VBAT_P12") (pintype "power_in"))
      (node (ref "U1M4") (pin "P12") (pinfunction "VBAT_P12") (pintype "power_in"))
    )
    (net (code "150") (name "unconnected-(1U1D-+IN-PadP11)") (class "Default")
      (node (ref "1U1") (pin "P11") (pinfunction "+IN_P11") (pintype "input"))
    )
    (net (code "151") (name "unconnected-(1U1D--IN-PadP10)") (class "Default")
      (node (ref "1U1") (pin "P10") (pinfunction "-IN_P10") (pintype "input"))
    )
    (net (code "152") (name "unconnected-(1U1D-OUT-PadP13)") (class "Default")
      (node (ref "1U1") (pin "P13") (pinfunction "OUT_P13") (pintype "output"))
    )
    (net (code "153") (name "unconnected-(4U2-ENA-Pad5)") (class "Default")
      (node (ref "4U2") (pin "5") (pinfunction "ENA_5") (pintype "input"))
    )
    (net (code "154") (name "unconnected-(4U2-NC-Pad2)") (class "Default")
      (node (ref "4U2") (pin "2") (pinfunction "NC_2") (pintype "no_connect"))
    )
    (net (code "155") (name "unconnected-(4U2-NC-Pad3)") (class "Default")
      (node (ref "4U2") (pin "3") (pinfunction "NC_3") (pintype "no_connect"))
    )
    (net (code "156") (name "unconnected-(IRIN1-Pad2)") (class "Default")
      (node (ref "IRIN1") (pin "2") (pinfunction "2_2") (pintype "passive"))
    )
    (net (code "157") (name "unconnected-(IRIN2-Pad2)") (class "Default")
      (node (ref "IRIN2") (pin "2") (pinfunction "2_2") (pintype "passive"))
    )
    (net (code "158") (name "unconnected-(J1M1-Pad2)") (class "Default")
      (node (ref "J1M1") (pin "2") (pinfunction "2_2") (pintype "passive"))
    )
    (net (code "159") (name "unconnected-(J1M2-Pad2)") (class "Default")
      (node (ref "J1M2") (pin "2") (pinfunction "2_2") (pintype "passive"))
    )
    (net (code "160") (name "unconnected-(J1M3-Pad2)") (class "Default")
      (node (ref "J1M3") (pin "2") (pinfunction "2_2") (pintype "passive"))
    )
    (net (code "161") (name "unconnected-(J1M4-Pad2)") (class "Default")
      (node (ref "J1M4") (pin "2") (pinfunction "2_2") (pintype "passive"))
    )
    (net (code "162") (name "unconnected-(J2-Pad2)") (class "Default")
      (node (ref "J2") (pin "2") (pinfunction "2_2") (pintype "passive"))
    )
    (net (code "163") (name "unconnected-(J6-Pad2)") (class "Default")
      (node (ref "J6") (pin "2") (pinfunction "2_2") (pintype "passive"))
    )
    (net (code "164") (name "unconnected-(LED48-Pad2)") (class "Default")
      (node (ref "LED48") (pin "2") (pinfunction "2_2") (pintype "passive"))
    )
    (net (code "165") (name "unconnected-(LED49-Pad2)") (class "Default")
      (node (ref "LED49") (pin "2") (pinfunction "2_2") (pintype "passive"))
    )
    (net (code "166") (name "unconnected-(U1M1-NC-PadP2)") (class "Default")
      (node (ref "U1M1") (pin "P2") (pinfunction "NC_P2") (pintype "no_connect"))
    )
    (net (code "167") (name "unconnected-(U1M1-NC-PadP14)") (class "Default")
      (node (ref "U1M1") (pin "P14") (pinfunction "NC_P14") (pintype "no_connect"))
    )
    (net (code "168") (name "unconnected-(U1M1-NC-PadP17)") (class "Default")
      (node (ref "U1M1") (pin "P17") (pinfunction "NC_P17") (pintype "no_connect"))
    )
    (net (code "169") (name "unconnected-(U1M1-NC-PadP22)") (class "Default")
      (node (ref "U1M1") (pin "P22") (pinfunction "NC_P22") (pintype "no_connect"))
    )
    (net (code "170") (name "unconnected-(U1M1-NC-PadP24)") (class "Default")
      (node (ref "U1M1") (pin "P24") (pinfunction "NC_P24") (pintype "no_connect"))
    )
    (net (code "171") (name "unconnected-(U1M1-NC-PadP29)") (class "Default")
      (node (ref "U1M1") (pin "P29") (pinfunction "NC_P29") (pintype "no_connect"))
    )
    (net (code "172") (name "unconnected-(U1M2-NC-PadP2)") (class "Default")
      (node (ref "U1M2") (pin "P2") (pinfunction "NC_P2") (pintype "no_connect"))
    )
    (net (code "173") (name "unconnected-(U1M2-NC-PadP14)") (class "Default")
      (node (ref "U1M2") (pin "P14") (pinfunction "NC_P14") (pintype "no_connect"))
    )
    (net (code "174") (name "unconnected-(U1M2-NC-PadP17)") (class "Default")
      (node (ref "U1M2") (pin "P17") (pinfunction "NC_P17") (pintype "no_connect"))
    )
    (net (code "175") (name "unconnected-(U1M2-NC-PadP22)") (class "Default")
      (node (ref "U1M2") (pin "P22") (pinfunction "NC_P22") (pintype "no_connect"))
    )
    (net (code "176") (name "unconnected-(U1M2-NC-PadP24)") (class "Default")
      (node (ref "U1M2") (pin "P24") (pinfunction "NC_P24") (pintype "no_connect"))
    )
    (net (code "177") (name "unconnected-(U1M2-NC-PadP29)") (class "Default")
      (node (ref "U1M2") (pin "P29") (pinfunction "NC_P29") (pintype "no_connect"))
    )
    (net (code "178") (name "unconnected-(U1M3-NC-PadP2)") (class "Default")
      (node (ref "U1M3") (pin "P2") (pinfunction "NC_P2") (pintype "no_connect"))
    )
    (net (code "179") (name "unconnected-(U1M3-NC-PadP14)") (class "Default")
      (node (ref "U1M3") (pin "P14") (pinfunction "NC_P14") (pintype "no_connect"))
    )
    (net (code "180") (name "unconnected-(U1M3-NC-PadP17)") (class "Default")
      (node (ref "U1M3") (pin "P17") (pinfunction "NC_P17") (pintype "no_connect"))
    )
    (net (code "181") (name "unconnected-(U1M3-NC-PadP22)") (class "Default")
      (node (ref "U1M3") (pin "P22") (pinfunction "NC_P22") (pintype "no_connect"))
    )
    (net (code "182") (name "unconnected-(U1M3-NC-PadP24)") (class "Default")
      (node (ref "U1M3") (pin "P24") (pinfunction "NC_P24") (pintype "no_connect"))
    )
    (net (code "183") (name "unconnected-(U1M3-NC-PadP29)") (class "Default")
      (node (ref "U1M3") (pin "P29") (pinfunction "NC_P29") (pintype "no_connect"))
    )
    (net (code "184") (name "unconnected-(U1M4-NC-PadP2)") (class "Default")
      (node (ref "U1M4") (pin "P2") (pinfunction "NC_P2") (pintype "no_connect"))
    )
    (net (code "185") (name "unconnected-(U1M4-NC-PadP14)") (class "Default")
      (node (ref "U1M4") (pin "P14") (pinfunction "NC_P14") (pintype "no_connect"))
    )
    (net (code "186") (name "unconnected-(U1M4-NC-PadP17)") (class "Default")
      (node (ref "U1M4") (pin "P17") (pinfunction "NC_P17") (pintype "no_connect"))
    )
    (net (code "187") (name "unconnected-(U1M4-NC-PadP22)") (class "Default")
      (node (ref "U1M4") (pin "P22") (pinfunction "NC_P22") (pintype "no_connect"))
    )
    (net (code "188") (name "unconnected-(U1M4-NC-PadP24)") (class "Default")
      (node (ref "U1M4") (pin "P24") (pinfunction "NC_P24") (pintype "no_connect"))
    )
    (net (code "189") (name "unconnected-(U1M4-NC-PadP29)") (class "Default")
      (node (ref "U1M4") (pin "P29") (pinfunction "NC_P29") (pintype "no_connect"))
    )
  )
)
